# InteractionBoard.net
KiCad netlist of a schematic drawn in EAGLE
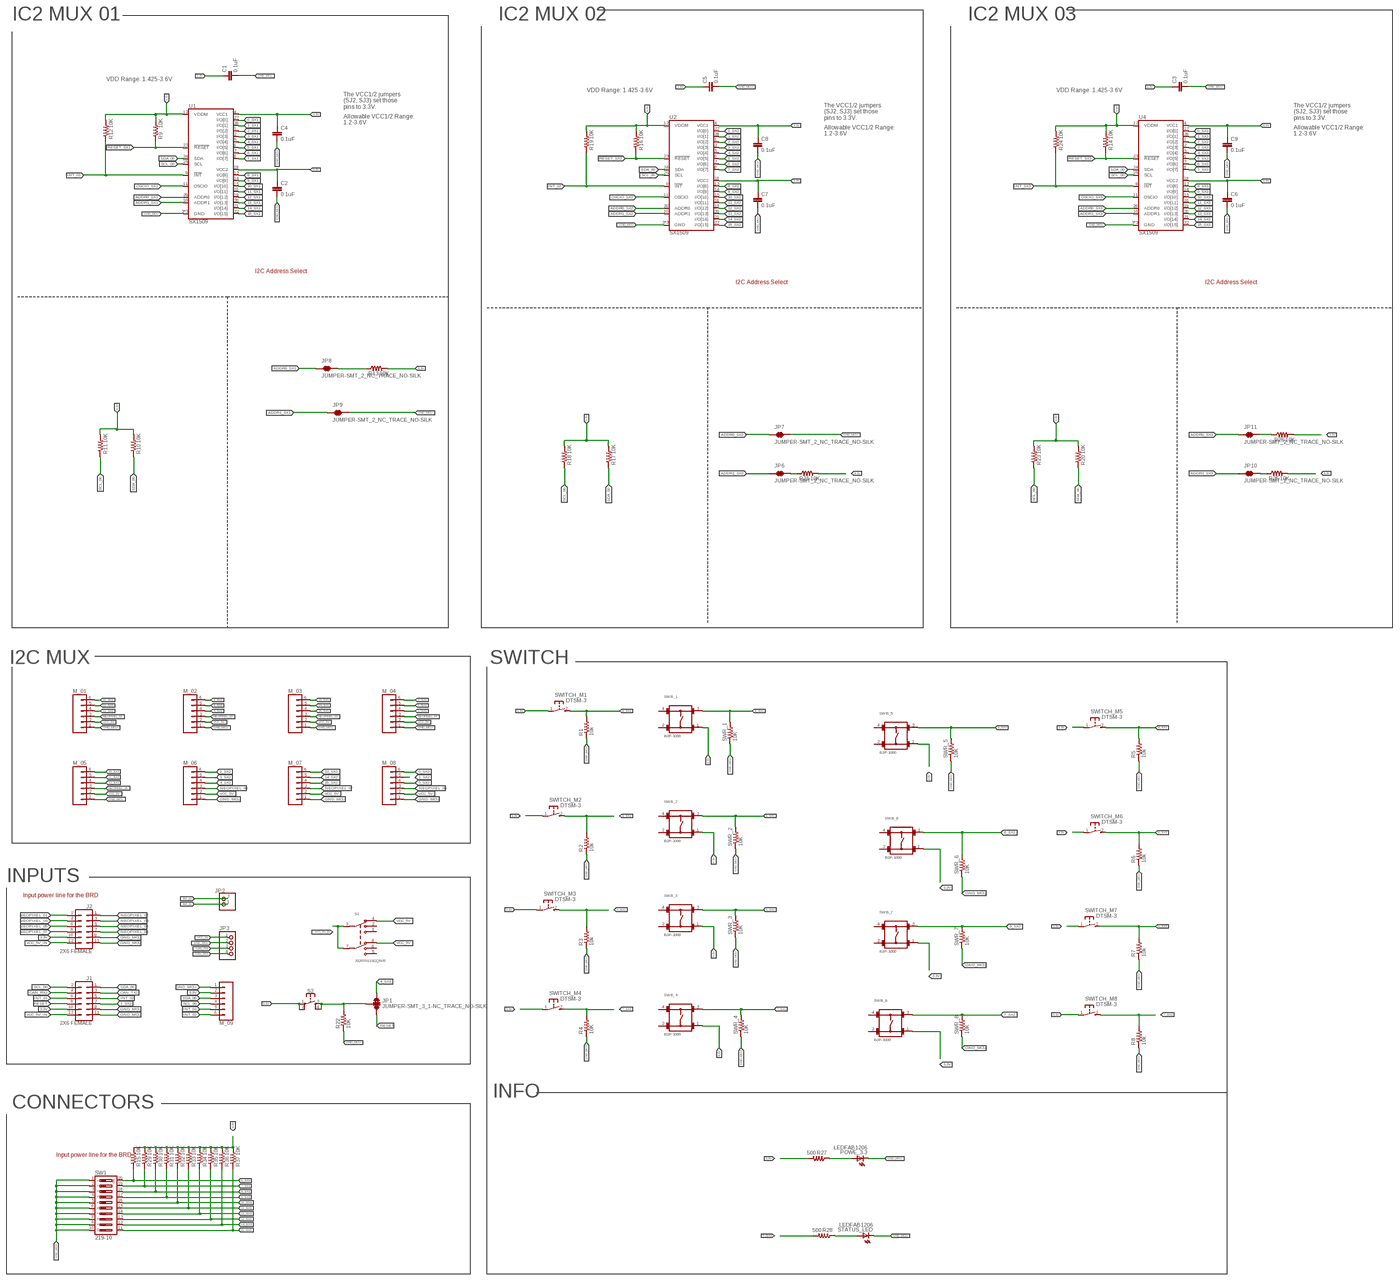
[diagram p0: schematic, sheet 1, overview]
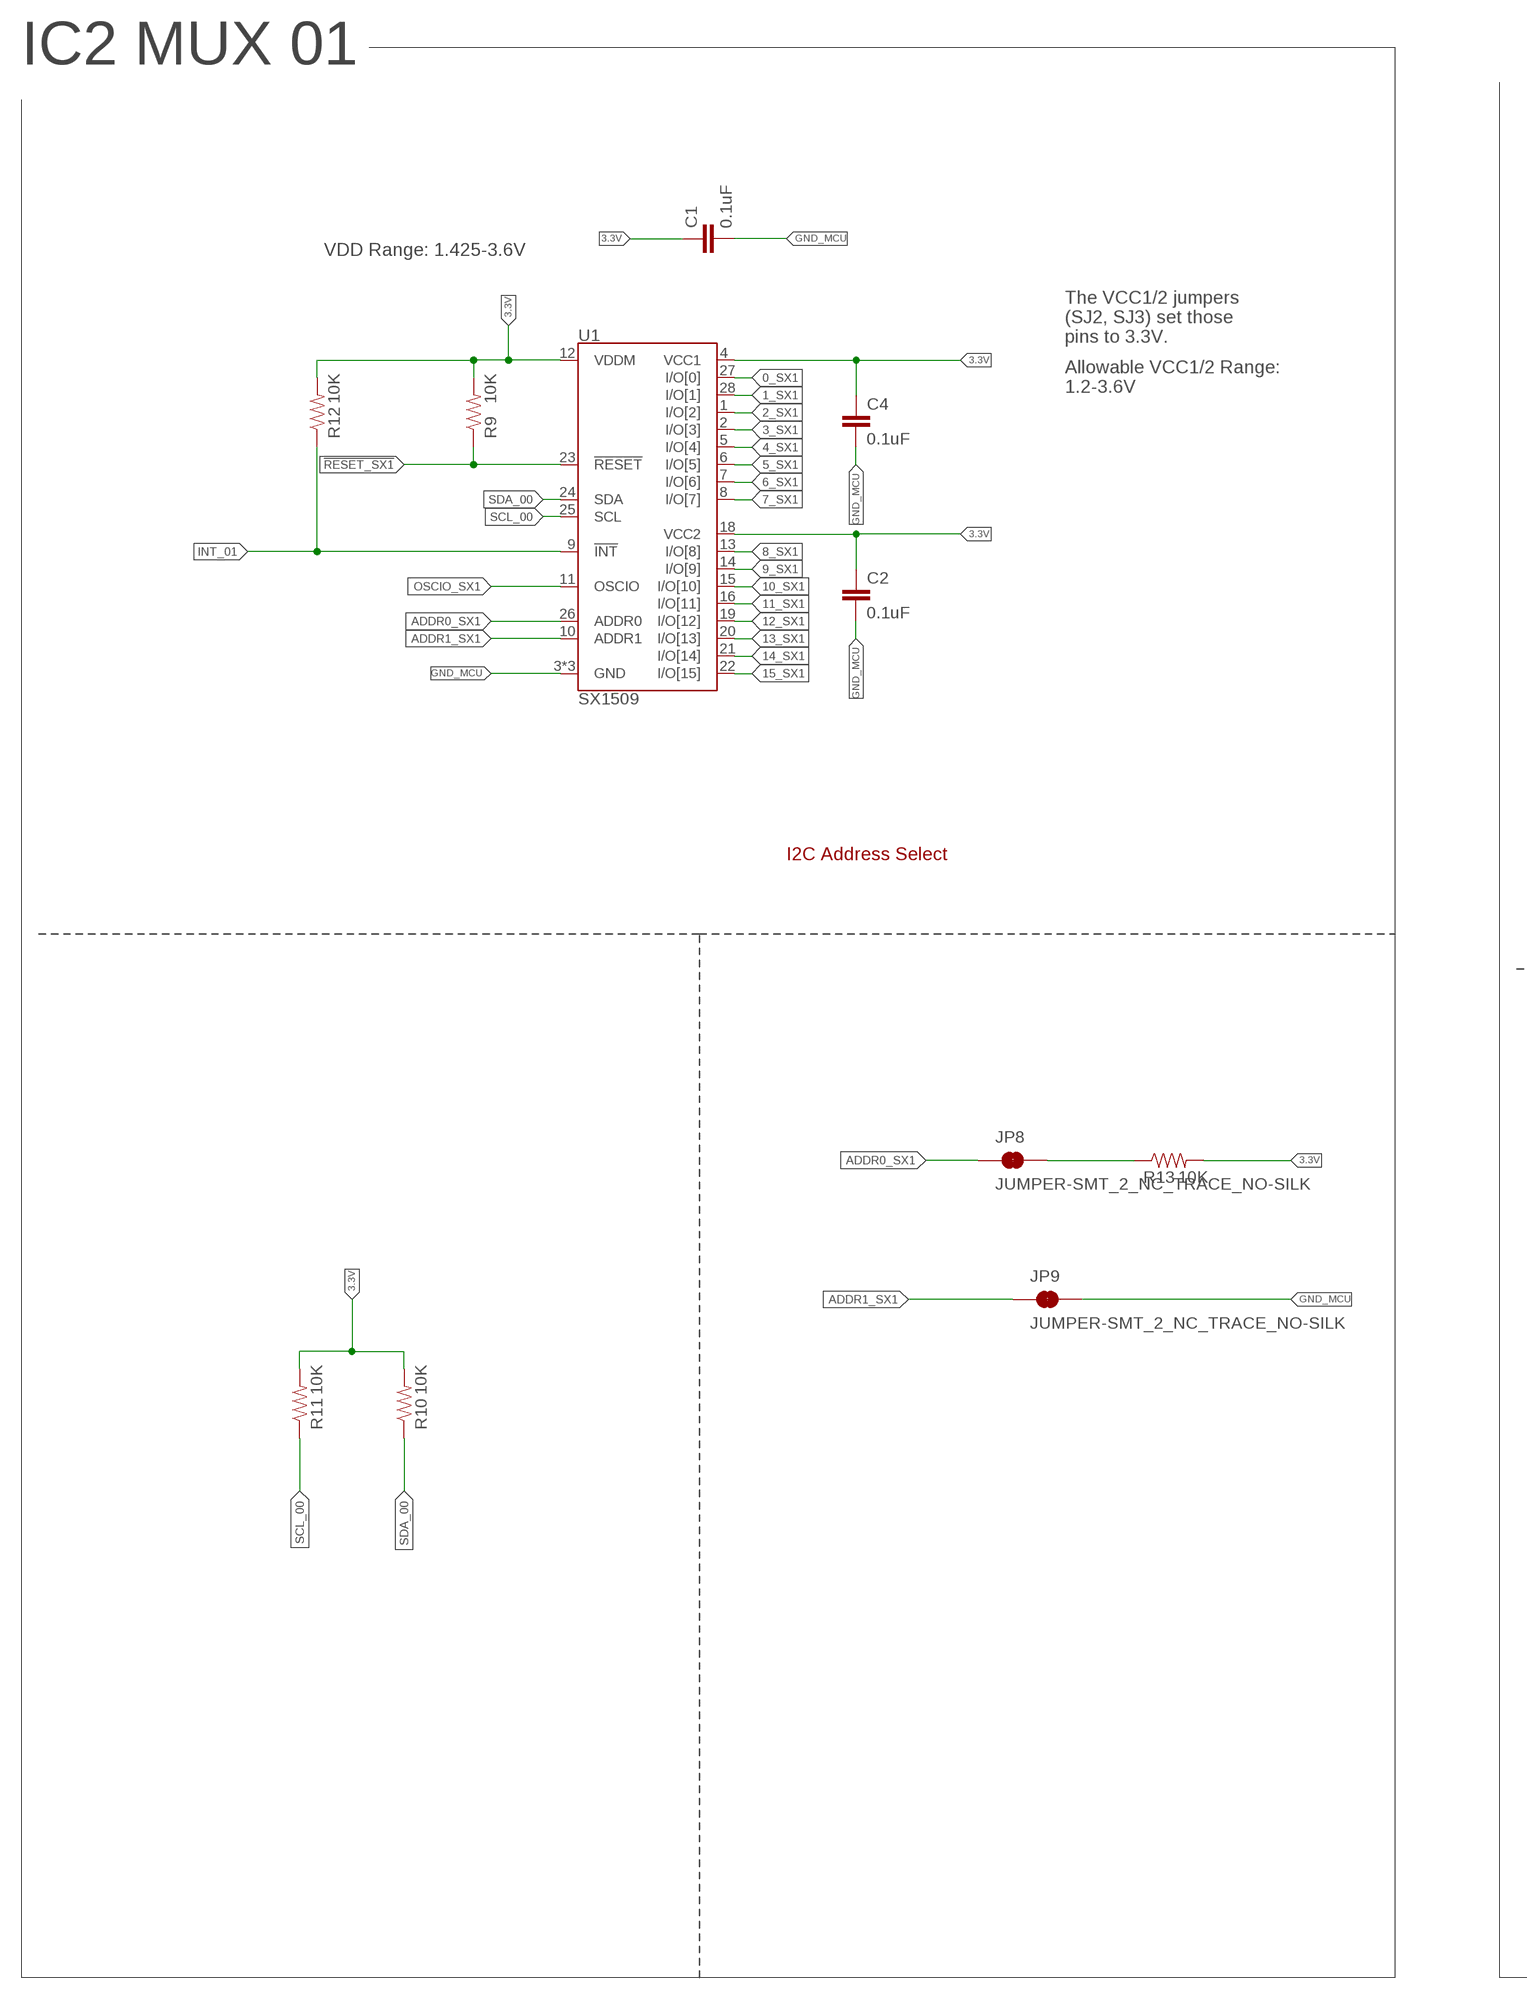
[diagram p1: schematic, sheet 1, part 1 of 4]
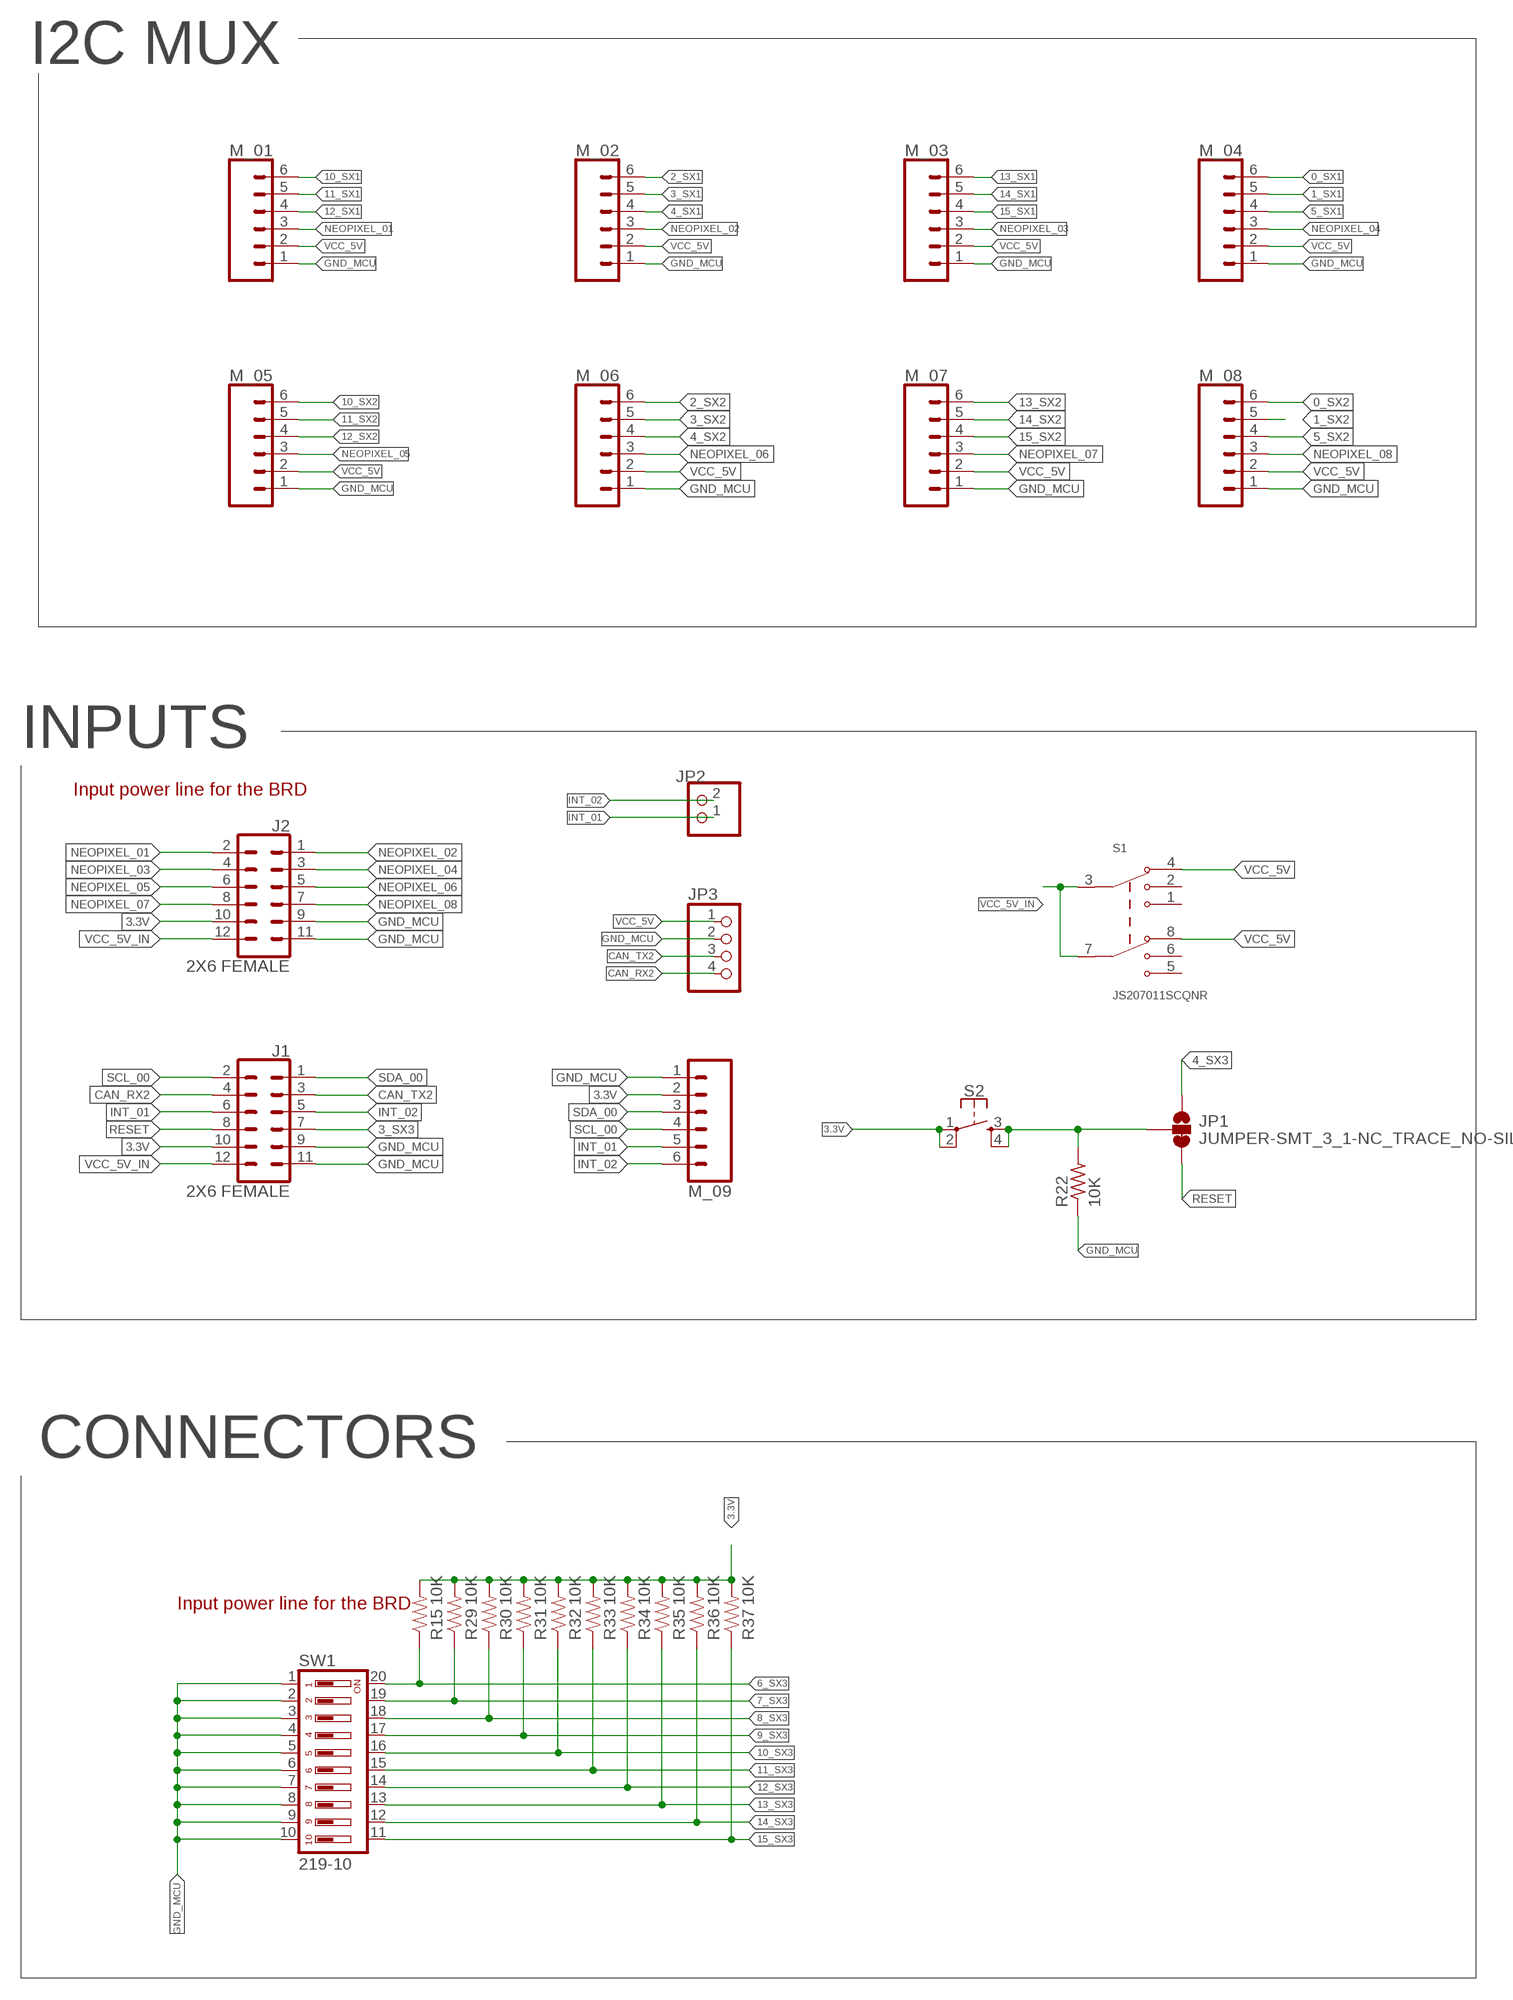
[diagram p2: schematic, sheet 1, part 2 of 4]
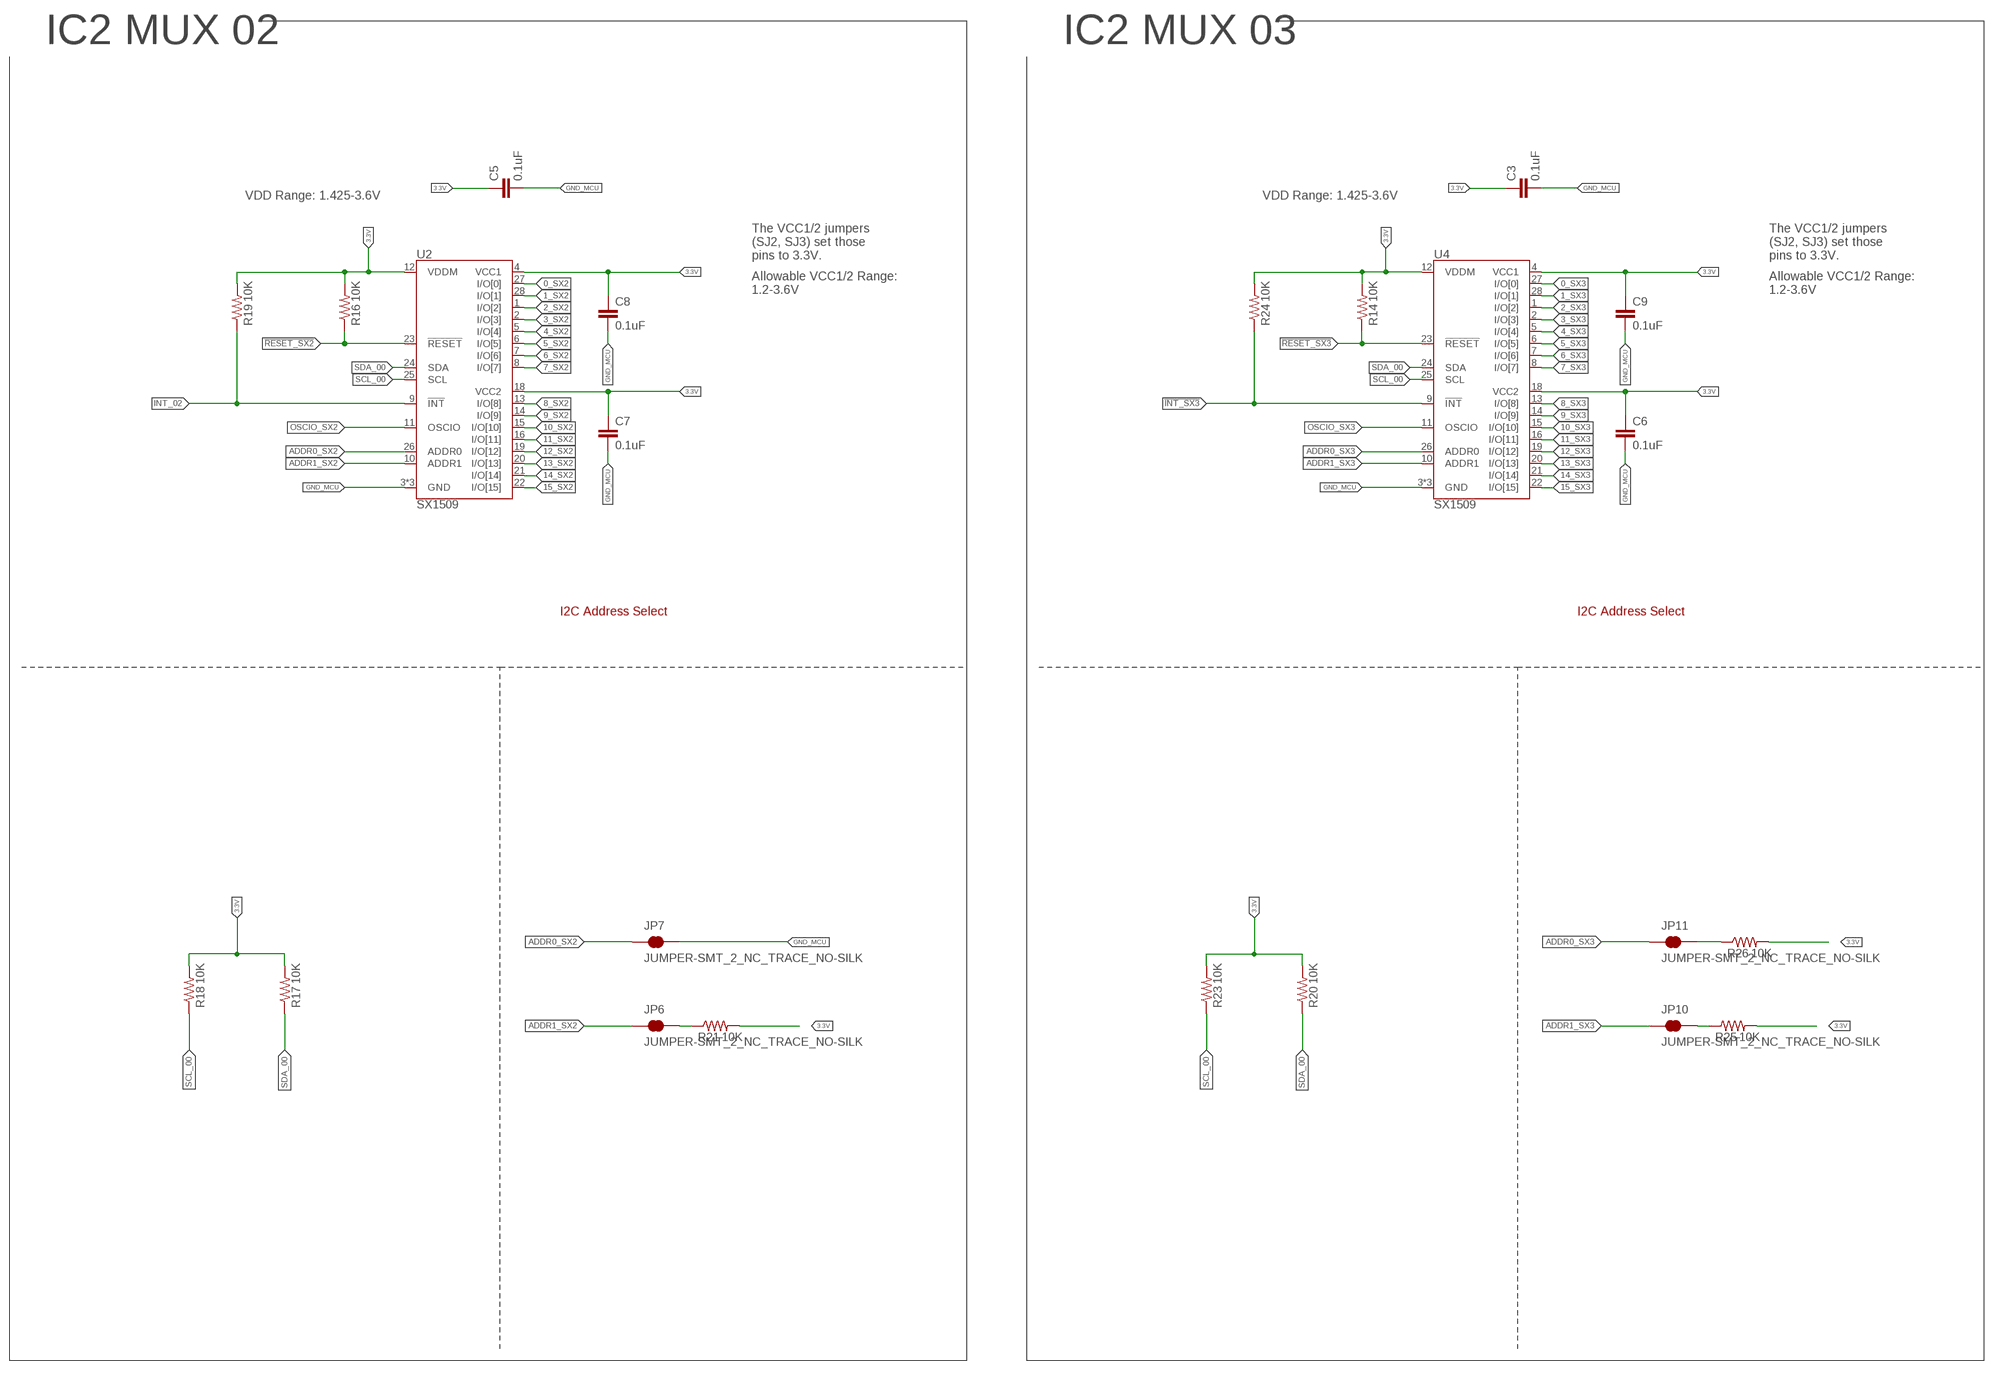
[diagram p3: schematic, sheet 1, part 3 of 4]
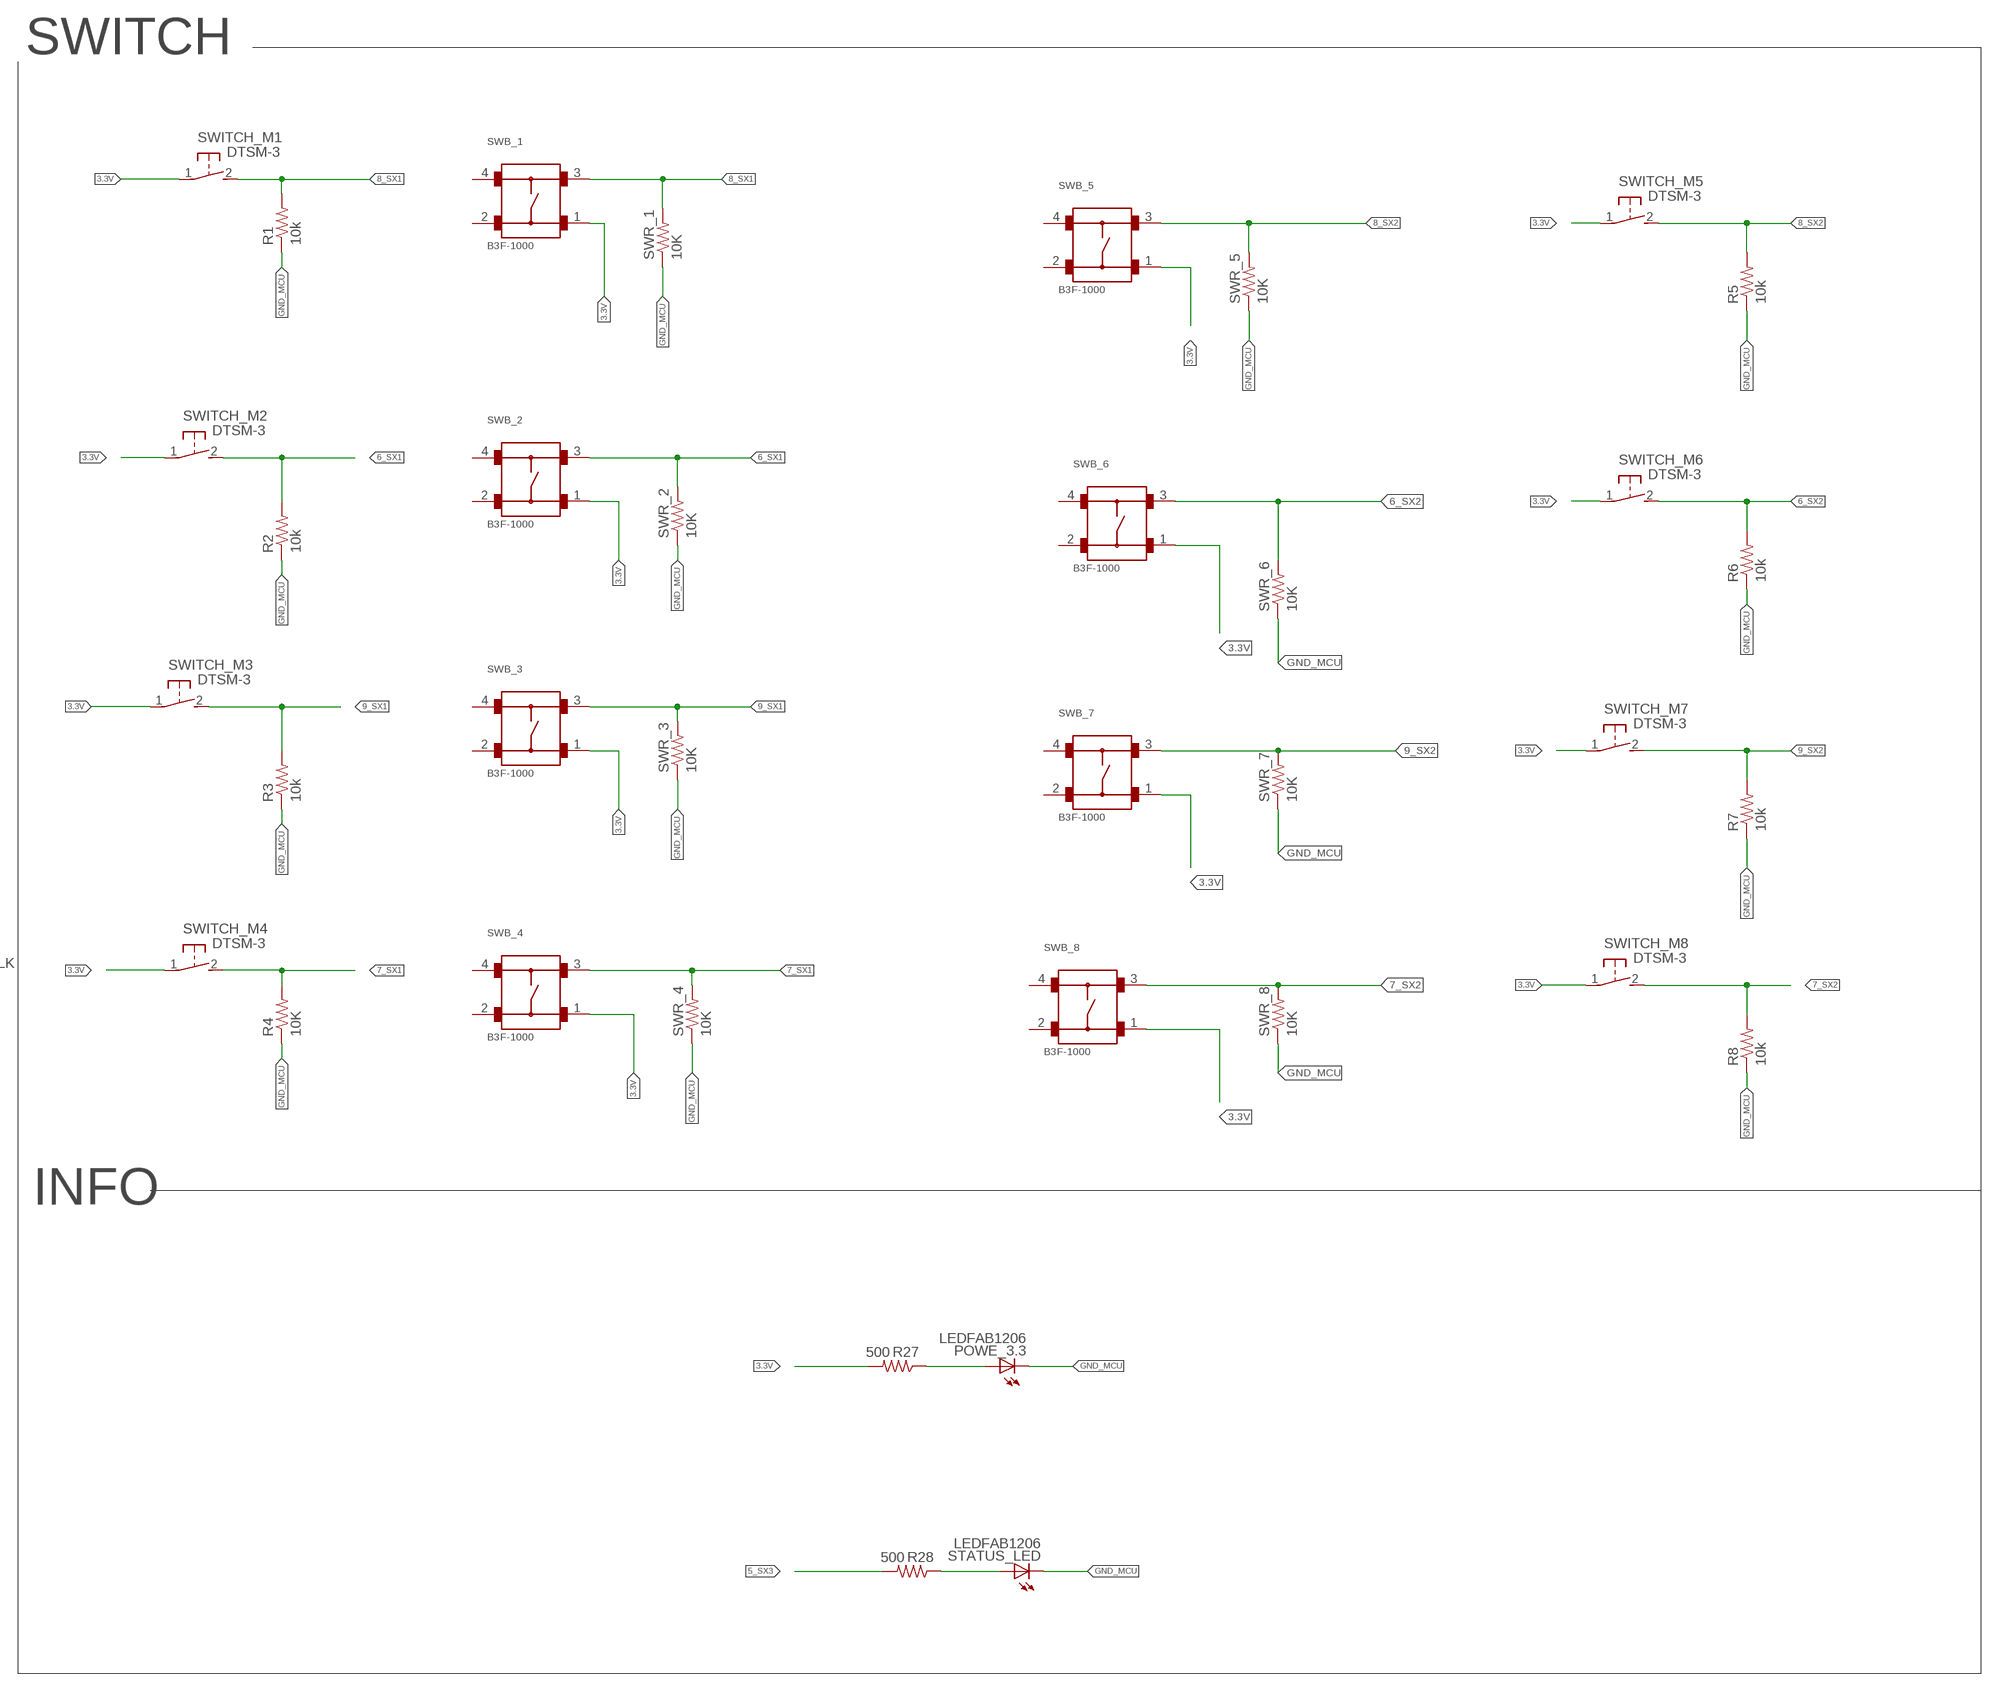
[diagram p4: schematic, sheet 1, part 4 of 4]

(export (version "E")
  (design (tool "Eeschema 10.0.6"))
  (components
    (comp (ref "C1")
      (value "0.1uF")
      (footprint "eagle-import:0603-CAP")
      (libsource (lib "eagle-import") (part "0.1UF-25V(+80/-20%)(0603)"))
    )
    (comp (ref "C2")
      (value "0.1uF")
      (footprint "eagle-import:0603-CAP")
      (libsource (lib "eagle-import") (part "0.1UF-25V(+80/-20%)(0603)"))
    )
    (comp (ref "C3")
      (value "0.1uF")
      (footprint "eagle-import:0603-CAP")
      (libsource (lib "eagle-import") (part "0.1UF-25V(+80/-20%)(0603)"))
    )
    (comp (ref "C4")
      (value "0.1uF")
      (footprint "eagle-import:0603-CAP")
      (libsource (lib "eagle-import") (part "0.1UF-25V(+80/-20%)(0603)"))
    )
    (comp (ref "C5")
      (value "0.1uF")
      (footprint "eagle-import:0603-CAP")
      (libsource (lib "eagle-import") (part "0.1UF-25V(+80/-20%)(0603)"))
    )
    (comp (ref "C6")
      (value "0.1uF")
      (footprint "eagle-import:0603-CAP")
      (libsource (lib "eagle-import") (part "0.1UF-25V(+80/-20%)(0603)"))
    )
    (comp (ref "C7")
      (value "0.1uF")
      (footprint "eagle-import:0603-CAP")
      (libsource (lib "eagle-import") (part "0.1UF-25V(+80/-20%)(0603)"))
    )
    (comp (ref "C8")
      (value "0.1uF")
      (footprint "eagle-import:0603-CAP")
      (libsource (lib "eagle-import") (part "0.1UF-25V(+80/-20%)(0603)"))
    )
    (comp (ref "C9")
      (value "0.1uF")
      (footprint "eagle-import:0603-CAP")
      (libsource (lib "eagle-import") (part "0.1UF-25V(+80/-20%)(0603)"))
    )
    (comp (ref "J1")
      (value "2X6 FEMALE")
      (footprint "eagle-import:2X6")
      (libsource (lib "eagle-import") (part "CONN_06X2PTH_FEMALE"))
    )
    (comp (ref "J2")
      (value "2X6 FEMALE")
      (footprint "eagle-import:2X6")
      (libsource (lib "eagle-import") (part "CONN_06X2PTH_FEMALE"))
    )
    (comp (ref "JP1")
      (value "JUMPER-SMT_3_1-NC_TRACE_NO-SILK")
      (footprint "eagle-import:SMT-JUMPER_3_1-NC_TRACE_NO-SILK")
      (libsource (lib "eagle-import") (part "JUMPER-SMT_3_1-NC_TRACE_NO-SILK"))
    )
    (comp (ref "JP2")
      (value "HEADER-1X2ROUND")
      (footprint "eagle-import:1X02_ROUND")
      (libsource (lib "eagle-import") (part "HEADER-1X2ROUND"))
    )
    (comp (ref "JP3")
      (value "HEADER-1X4ROUND")
      (footprint "eagle-import:1X04_ROUND")
      (libsource (lib "eagle-import") (part "HEADER-1X4ROUND"))
    )
    (comp (ref "JP6")
      (value "JUMPER-SMT_2_NC_TRACE_NO-SILK")
      (footprint "eagle-import:SMT-JUMPER_2_NC_TRACE_NO-SILK")
      (libsource (lib "eagle-import") (part "JUMPER-SMT_2_NC_TRACE_NO-SILK"))
    )
    (comp (ref "JP7")
      (value "JUMPER-SMT_2_NC_TRACE_NO-SILK")
      (footprint "eagle-import:SMT-JUMPER_2_NC_TRACE_NO-SILK")
      (libsource (lib "eagle-import") (part "JUMPER-SMT_2_NC_TRACE_NO-SILK"))
    )
    (comp (ref "JP8")
      (value "JUMPER-SMT_2_NC_TRACE_NO-SILK")
      (footprint "eagle-import:SMT-JUMPER_2_NC_TRACE_NO-SILK")
      (libsource (lib "eagle-import") (part "JUMPER-SMT_2_NC_TRACE_NO-SILK"))
    )
    (comp (ref "JP9")
      (value "JUMPER-SMT_2_NC_TRACE_NO-SILK")
      (footprint "eagle-import:SMT-JUMPER_2_NC_TRACE_NO-SILK")
      (libsource (lib "eagle-import") (part "JUMPER-SMT_2_NC_TRACE_NO-SILK"))
    )
    (comp (ref "JP10")
      (value "JUMPER-SMT_2_NC_TRACE_NO-SILK")
      (footprint "eagle-import:SMT-JUMPER_2_NC_TRACE_NO-SILK")
      (libsource (lib "eagle-import") (part "JUMPER-SMT_2_NC_TRACE_NO-SILK"))
    )
    (comp (ref "JP11")
      (value "JUMPER-SMT_2_NC_TRACE_NO-SILK")
      (footprint "eagle-import:SMT-JUMPER_2_NC_TRACE_NO-SILK")
      (libsource (lib "eagle-import") (part "JUMPER-SMT_2_NC_TRACE_NO-SILK"))
    )
    (comp (ref "M_01")
      (value "CONN_06SMD-1MM")
      (footprint "eagle-import:1X06-1MM")
      (libsource (lib "eagle-import") (part "CONN_06SMD-1MM"))
    )
    (comp (ref "M_02")
      (value "CONN_06SMD-1MM")
      (footprint "eagle-import:1X06-1MM")
      (libsource (lib "eagle-import") (part "CONN_06SMD-1MM"))
    )
    (comp (ref "M_03")
      (value "CONN_06SMD-1MM")
      (footprint "eagle-import:1X06-1MM")
      (libsource (lib "eagle-import") (part "CONN_06SMD-1MM"))
    )
    (comp (ref "M_04")
      (value "CONN_06SMD-1MM")
      (footprint "eagle-import:1X06-1MM")
      (libsource (lib "eagle-import") (part "CONN_06SMD-1MM"))
    )
    (comp (ref "M_05")
      (value "CONN_06SMD-1MM")
      (footprint "eagle-import:1X06-1MM")
      (libsource (lib "eagle-import") (part "CONN_06SMD-1MM"))
    )
    (comp (ref "M_06")
      (value "CONN_06SMD-1MM")
      (footprint "eagle-import:1X06-1MM")
      (libsource (lib "eagle-import") (part "CONN_06SMD-1MM"))
    )
    (comp (ref "M_07")
      (value "CONN_06SMD-1MM")
      (footprint "eagle-import:1X06-1MM")
      (libsource (lib "eagle-import") (part "CONN_06SMD-1MM"))
    )
    (comp (ref "M_08")
      (value "CONN_06SMD-1MM")
      (footprint "eagle-import:1X06-1MM")
      (libsource (lib "eagle-import") (part "CONN_06SMD-1MM"))
    )
    (comp (ref "M_09")
      (value "CONN_06SMD-1MM")
      (footprint "eagle-import:1X06-1MM")
      (libsource (lib "eagle-import") (part "CONN_06SMD-1MM"))
    )
    (comp (ref "POWE_3.3")
      (value "LEDFAB1206")
      (footprint "eagle-import:LED1206FAB")
      (libsource (lib "eagle-import") (part "LEDFAB1206"))
    )
    (comp (ref "R1")
      (value "10k")
      (footprint "eagle-import:M0805")
      (libsource (lib "eagle-import") (part "R-US_M0805"))
    )
    (comp (ref "R2")
      (value "10k")
      (footprint "eagle-import:M0805")
      (libsource (lib "eagle-import") (part "R-US_M0805"))
    )
    (comp (ref "R3")
      (value "10k")
      (footprint "eagle-import:M0805")
      (libsource (lib "eagle-import") (part "R-US_M0805"))
    )
    (comp (ref "R4")
      (value "10K")
      (footprint "eagle-import:M0805")
      (libsource (lib "eagle-import") (part "R-US_M0805"))
    )
    (comp (ref "R5")
      (value "10k")
      (footprint "eagle-import:M0805")
      (libsource (lib "eagle-import") (part "R-US_M0805"))
    )
    (comp (ref "R6")
      (value "10k")
      (footprint "eagle-import:M0805")
      (libsource (lib "eagle-import") (part "R-US_M0805"))
    )
    (comp (ref "R7")
      (value "10k")
      (footprint "eagle-import:M0805")
      (libsource (lib "eagle-import") (part "R-US_M0805"))
    )
    (comp (ref "R8")
      (value "10k")
      (footprint "eagle-import:M0805")
      (libsource (lib "eagle-import") (part "R-US_M0805"))
    )
    (comp (ref "R9")
      (value "10K")
      (footprint "eagle-import:0603-RES")
      (libsource (lib "eagle-import") (part "SparkFun-Resistors_532_10KOHM-1/10W-1%(0603)0603"))
    )
    (comp (ref "R10")
      (value "10K")
      (footprint "eagle-import:0603-RES")
      (libsource (lib "eagle-import") (part "SparkFun-Resistors_532_10KOHM-1/10W-1%(0603)0603"))
    )
    (comp (ref "R11")
      (value "10K")
      (footprint "eagle-import:0603-RES")
      (libsource (lib "eagle-import") (part "SparkFun-Resistors_532_10KOHM-1/10W-1%(0603)0603"))
    )
    (comp (ref "R12")
      (value "10K")
      (footprint "eagle-import:0603-RES")
      (libsource (lib "eagle-import") (part "SparkFun-Resistors_532_10KOHM-1/10W-1%(0603)0603"))
    )
    (comp (ref "R13")
      (value "10K")
      (footprint "eagle-import:0603-RES")
      (libsource (lib "eagle-import") (part "SparkFun-Resistors_532_10KOHM-1/10W-1%(0603)0603"))
    )
    (comp (ref "R14")
      (value "10K")
      (footprint "eagle-import:0603-RES")
      (libsource (lib "eagle-import") (part "SparkFun-Resistors_532_10KOHM-1/10W-1%(0603)0603"))
    )
    (comp (ref "R15")
      (value "10K")
      (footprint "eagle-import:0603-RES")
      (libsource (lib "eagle-import") (part "SparkFun-Resistors_532_10KOHM-1/10W-1%(0603)0603"))
    )
    (comp (ref "R16")
      (value "10K")
      (footprint "eagle-import:0603-RES")
      (libsource (lib "eagle-import") (part "SparkFun-Resistors_532_10KOHM-1/10W-1%(0603)0603"))
    )
    (comp (ref "R17")
      (value "10K")
      (footprint "eagle-import:0603-RES")
      (libsource (lib "eagle-import") (part "SparkFun-Resistors_532_10KOHM-1/10W-1%(0603)0603"))
    )
    (comp (ref "R18")
      (value "10K")
      (footprint "eagle-import:0603-RES")
      (libsource (lib "eagle-import") (part "SparkFun-Resistors_532_10KOHM-1/10W-1%(0603)0603"))
    )
    (comp (ref "R19")
      (value "10K")
      (footprint "eagle-import:0603-RES")
      (libsource (lib "eagle-import") (part "SparkFun-Resistors_532_10KOHM-1/10W-1%(0603)0603"))
    )
    (comp (ref "R20")
      (value "10K")
      (footprint "eagle-import:0603-RES")
      (libsource (lib "eagle-import") (part "SparkFun-Resistors_532_10KOHM-1/10W-1%(0603)0603"))
    )
    (comp (ref "R21")
      (value "10K")
      (footprint "eagle-import:0603-RES")
      (libsource (lib "eagle-import") (part "SparkFun-Resistors_532_10KOHM-1/10W-1%(0603)0603"))
    )
    (comp (ref "R22")
      (value "10K")
      (footprint "eagle-import:M0805")
      (libsource (lib "eagle-import") (part "R-US_M0805"))
    )
    (comp (ref "R23")
      (value "10K")
      (footprint "eagle-import:0603-RES")
      (libsource (lib "eagle-import") (part "SparkFun-Resistors_532_10KOHM-1/10W-1%(0603)0603"))
    )
    (comp (ref "R24")
      (value "10K")
      (footprint "eagle-import:0603-RES")
      (libsource (lib "eagle-import") (part "SparkFun-Resistors_532_10KOHM-1/10W-1%(0603)0603"))
    )
    (comp (ref "R25")
      (value "10K")
      (footprint "eagle-import:0603-RES")
      (libsource (lib "eagle-import") (part "SparkFun-Resistors_532_10KOHM-1/10W-1%(0603)0603"))
    )
    (comp (ref "R26")
      (value "10K")
      (footprint "eagle-import:0603-RES")
      (libsource (lib "eagle-import") (part "SparkFun-Resistors_532_10KOHM-1/10W-1%(0603)0603"))
    )
    (comp (ref "R27")
      (value "500")
      (footprint "eagle-import:0603-RES")
      (libsource (lib "eagle-import") (part "10KOHM-1/10W-1%(0603)0603"))
    )
    (comp (ref "R28")
      (value "500")
      (footprint "eagle-import:0603-RES")
      (libsource (lib "eagle-import") (part "10KOHM-1/10W-1%(0603)0603"))
    )
    (comp (ref "R29")
      (value "10K")
      (footprint "eagle-import:0603-RES")
      (libsource (lib "eagle-import") (part "SparkFun-Resistors_532_10KOHM-1/10W-1%(0603)0603"))
    )
    (comp (ref "R30")
      (value "10K")
      (footprint "eagle-import:0603-RES")
      (libsource (lib "eagle-import") (part "SparkFun-Resistors_532_10KOHM-1/10W-1%(0603)0603"))
    )
    (comp (ref "R31")
      (value "10K")
      (footprint "eagle-import:0603-RES")
      (libsource (lib "eagle-import") (part "SparkFun-Resistors_532_10KOHM-1/10W-1%(0603)0603"))
    )
    (comp (ref "R32")
      (value "10K")
      (footprint "eagle-import:0603-RES")
      (libsource (lib "eagle-import") (part "SparkFun-Resistors_532_10KOHM-1/10W-1%(0603)0603"))
    )
    (comp (ref "R33")
      (value "10K")
      (footprint "eagle-import:0603-RES")
      (libsource (lib "eagle-import") (part "SparkFun-Resistors_532_10KOHM-1/10W-1%(0603)0603"))
    )
    (comp (ref "R34")
      (value "10K")
      (footprint "eagle-import:0603-RES")
      (libsource (lib "eagle-import") (part "SparkFun-Resistors_532_10KOHM-1/10W-1%(0603)0603"))
    )
    (comp (ref "R35")
      (value "10K")
      (footprint "eagle-import:0603-RES")
      (libsource (lib "eagle-import") (part "SparkFun-Resistors_532_10KOHM-1/10W-1%(0603)0603"))
    )
    (comp (ref "R36")
      (value "10K")
      (footprint "eagle-import:0603-RES")
      (libsource (lib "eagle-import") (part "SparkFun-Resistors_532_10KOHM-1/10W-1%(0603)0603"))
    )
    (comp (ref "R37")
      (value "10K")
      (footprint "eagle-import:0603-RES")
      (libsource (lib "eagle-import") (part "SparkFun-Resistors_532_10KOHM-1/10W-1%(0603)0603"))
    )
    (comp (ref "S1")
      (value "JS207011SCQNR")
      (footprint "eagle-import:SW_JS207011SCQNR")
      (fields (field (name "MF") "C&K"))
      (libsource (lib "eagle-import") (part "JS207011SCQNR"))
    )
    (comp (ref "S2")
      (value "MOMENTARY-SWITCH-SPST-2-SMD-5.2MM")
      (footprint "eagle-import:TACTILE_SWITCH_SMD_5.2MM")
      (libsource (lib "eagle-import") (part "MOMENTARY-SWITCH-SPST-2-SMD-5.2MM"))
    )
    (comp (ref "STATUS_LED")
      (value "LEDFAB1206")
      (footprint "eagle-import:LED1206FAB")
      (libsource (lib "eagle-import") (part "LEDFAB1206"))
    )
    (comp (ref "SW1")
      (value "219-10")
      (footprint "eagle-import:CTS-219-10")
      (fields (field (name "MF") "SLI (CML/IDI)") (field (name "MPN") "219-10PK"))
      (libsource (lib "eagle-import") (part "219-10"))
    )
    (comp (ref "SWB_1")
      (value "B3F-1000")
      (footprint "eagle-import:B3F-1000")
      (fields
        (field (name "DIGI_KEY_PART_NUMBER") "SW400-ND")
        (field (name "MANUFACTURER") "Omron Electronics Inc-EMC Div")
        (field (name "CREATED_BY") "PCBLayout.com")
      )
      (libsource (lib "eagle-import") (part "B3F-1000"))
    )
    (comp (ref "SWB_2")
      (value "B3F-1000")
      (footprint "eagle-import:B3F-1000")
      (fields
        (field (name "DIGI_KEY_PART_NUMBER") "SW400-ND")
        (field (name "MANUFACTURER") "Omron Electronics Inc-EMC Div")
        (field (name "CREATED_BY") "PCBLayout.com")
      )
      (libsource (lib "eagle-import") (part "B3F-1000"))
    )
    (comp (ref "SWB_3")
      (value "B3F-1000")
      (footprint "eagle-import:B3F-1000")
      (fields
        (field (name "DIGI_KEY_PART_NUMBER") "SW400-ND")
        (field (name "MANUFACTURER") "Omron Electronics Inc-EMC Div")
        (field (name "CREATED_BY") "PCBLayout.com")
      )
      (libsource (lib "eagle-import") (part "B3F-1000"))
    )
    (comp (ref "SWB_4")
      (value "B3F-1000")
      (footprint "eagle-import:B3F-1000")
      (fields
        (field (name "DIGI_KEY_PART_NUMBER") "SW400-ND")
        (field (name "MANUFACTURER") "Omron Electronics Inc-EMC Div")
        (field (name "CREATED_BY") "PCBLayout.com")
      )
      (libsource (lib "eagle-import") (part "B3F-1000"))
    )
    (comp (ref "SWB_5")
      (value "B3F-1000")
      (footprint "eagle-import:B3F-1000")
      (fields
        (field (name "DIGI_KEY_PART_NUMBER") "SW400-ND")
        (field (name "MANUFACTURER") "Omron Electronics Inc-EMC Div")
        (field (name "CREATED_BY") "PCBLayout.com")
      )
      (libsource (lib "eagle-import") (part "B3F-1000"))
    )
    (comp (ref "SWB_6")
      (value "B3F-1000")
      (footprint "eagle-import:B3F-1000")
      (fields
        (field (name "DIGI_KEY_PART_NUMBER") "SW400-ND")
        (field (name "MANUFACTURER") "Omron Electronics Inc-EMC Div")
        (field (name "CREATED_BY") "PCBLayout.com")
      )
      (libsource (lib "eagle-import") (part "B3F-1000"))
    )
    (comp (ref "SWB_7")
      (value "B3F-1000")
      (footprint "eagle-import:B3F-1000")
      (fields
        (field (name "DIGI_KEY_PART_NUMBER") "SW400-ND")
        (field (name "MANUFACTURER") "Omron Electronics Inc-EMC Div")
        (field (name "CREATED_BY") "PCBLayout.com")
      )
      (libsource (lib "eagle-import") (part "B3F-1000"))
    )
    (comp (ref "SWB_8")
      (value "B3F-1000")
      (footprint "eagle-import:B3F-1000")
      (fields
        (field (name "DIGI_KEY_PART_NUMBER") "SW400-ND")
        (field (name "MANUFACTURER") "Omron Electronics Inc-EMC Div")
        (field (name "CREATED_BY") "PCBLayout.com")
      )
      (libsource (lib "eagle-import") (part "B3F-1000"))
    )
    (comp (ref "SWITCH_M1")
      (value "DTSM-3")
      (footprint "eagle-import:DTSM-3")
      (libsource (lib "eagle-import") (part "DTSM-3"))
    )
    (comp (ref "SWITCH_M2")
      (value "DTSM-3")
      (footprint "eagle-import:DTSM-3")
      (libsource (lib "eagle-import") (part "DTSM-3"))
    )
    (comp (ref "SWITCH_M3")
      (value "DTSM-3")
      (footprint "eagle-import:DTSM-3")
      (libsource (lib "eagle-import") (part "DTSM-3"))
    )
    (comp (ref "SWITCH_M4")
      (value "DTSM-3")
      (footprint "eagle-import:DTSM-3")
      (libsource (lib "eagle-import") (part "DTSM-3"))
    )
    (comp (ref "SWITCH_M5")
      (value "DTSM-3")
      (footprint "eagle-import:DTSM-3")
      (libsource (lib "eagle-import") (part "DTSM-3"))
    )
    (comp (ref "SWITCH_M6")
      (value "DTSM-3")
      (footprint "eagle-import:DTSM-3")
      (libsource (lib "eagle-import") (part "DTSM-3"))
    )
    (comp (ref "SWITCH_M7")
      (value "DTSM-3")
      (footprint "eagle-import:DTSM-3")
      (libsource (lib "eagle-import") (part "DTSM-3"))
    )
    (comp (ref "SWITCH_M8")
      (value "DTSM-3")
      (footprint "eagle-import:DTSM-3")
      (libsource (lib "eagle-import") (part "DTSM-3"))
    )
    (comp (ref "SWR_1")
      (value "10K")
      (footprint "eagle-import:M0805")
      (libsource (lib "eagle-import") (part "R-US_M0805"))
    )
    (comp (ref "SWR_2")
      (value "10K")
      (footprint "eagle-import:M0805")
      (libsource (lib "eagle-import") (part "R-US_M0805"))
    )
    (comp (ref "SWR_3")
      (value "10K")
      (footprint "eagle-import:M0805")
      (libsource (lib "eagle-import") (part "R-US_M0805"))
    )
    (comp (ref "SWR_4")
      (value "10K")
      (footprint "eagle-import:M0805")
      (libsource (lib "eagle-import") (part "R-US_M0805"))
    )
    (comp (ref "SWR_5")
      (value "10K")
      (footprint "eagle-import:M0805")
      (libsource (lib "eagle-import") (part "R-US_M0805"))
    )
    (comp (ref "SWR_6")
      (value "10K")
      (footprint "eagle-import:M0805")
      (libsource (lib "eagle-import") (part "R-US_M0805"))
    )
    (comp (ref "SWR_7")
      (value "10K")
      (footprint "eagle-import:M0805")
      (libsource (lib "eagle-import") (part "R-US_M0805"))
    )
    (comp (ref "SWR_8")
      (value "10K")
      (footprint "eagle-import:M0805")
      (libsource (lib "eagle-import") (part "R-US_M0805"))
    )
    (comp (ref "U1")
      (value "SX1509")
      (footprint "eagle-import:QFN-28")
      (libsource (lib "eagle-import") (part "SX1509"))
    )
    (comp (ref "U2")
      (value "SX1509")
      (footprint "eagle-import:QFN-28")
      (libsource (lib "eagle-import") (part "SX1509"))
    )
    (comp (ref "U4")
      (value "SX1509")
      (footprint "eagle-import:QFN-28")
      (libsource (lib "eagle-import") (part "SX1509"))
    )
  )
  (nets
    (net (code "1") (name "/~{INT_SX3}") (class "Default")
      (node (ref "R24") (pin "1") (pinfunction "1_1") (pintype "passive"))
      (node (ref "U4") (pin "9") (pinfunction "~{INT}_9") (pintype "bidirectional"))
    )
    (net (code "2") (name "/~{RESET_SX1}") (class "Default")
      (node (ref "R9") (pin "1") (pinfunction "1_1") (pintype "passive"))
      (node (ref "U1") (pin "23") (pinfunction "~{RESET}_23") (pintype "bidirectional"))
    )
    (net (code "3") (name "/~{RESET_SX2}") (class "Default")
      (node (ref "R16") (pin "1") (pinfunction "1_1") (pintype "passive"))
      (node (ref "U2") (pin "23") (pinfunction "~{RESET}_23") (pintype "bidirectional"))
    )
    (net (code "4") (name "/~{RESET_SX3}") (class "Default")
      (node (ref "R14") (pin "1") (pinfunction "1_1") (pintype "passive"))
      (node (ref "U4") (pin "23") (pinfunction "~{RESET}_23") (pintype "bidirectional"))
    )
    (net (code "5") (name "0_SX1") (class "Default")
      (node (ref "M_04") (pin "6") (pinfunction "6_6") (pintype "passive"))
      (node (ref "U1") (pin "27") (pinfunction "I/O[0]_27") (pintype "bidirectional"))
    )
    (net (code "6") (name "0_SX2") (class "Default")
      (node (ref "M_08") (pin "6") (pinfunction "6_6") (pintype "passive"))
      (node (ref "U2") (pin "27") (pinfunction "I/O[0]_27") (pintype "bidirectional"))
    )
    (net (code "7") (name "0_SX3") (class "Default")
      (node (ref "U4") (pin "27") (pinfunction "I/O[0]_27") (pintype "bidirectional"))
    )
    (net (code "8") (name "1_SX1") (class "Default")
      (node (ref "M_04") (pin "5") (pinfunction "5_5") (pintype "passive"))
      (node (ref "U1") (pin "28") (pinfunction "I/O[1]_28") (pintype "bidirectional"))
    )
    (net (code "9") (name "1_SX2") (class "Default")
      (node (ref "M_08") (pin "5") (pinfunction "5_5") (pintype "passive"))
      (node (ref "U2") (pin "28") (pinfunction "I/O[1]_28") (pintype "bidirectional"))
    )
    (net (code "10") (name "1_SX3") (class "Default")
      (node (ref "U4") (pin "28") (pinfunction "I/O[1]_28") (pintype "bidirectional"))
    )
    (net (code "11") (name "2_SX1") (class "Default")
      (node (ref "M_02") (pin "6") (pinfunction "6_6") (pintype "passive"))
      (node (ref "U1") (pin "1") (pinfunction "I/O[2]_1") (pintype "bidirectional"))
    )
    (net (code "12") (name "2_SX2") (class "Default")
      (node (ref "M_06") (pin "6") (pinfunction "6_6") (pintype "passive"))
      (node (ref "U2") (pin "1") (pinfunction "I/O[2]_1") (pintype "bidirectional"))
    )
    (net (code "13") (name "2_SX3") (class "Default")
      (node (ref "U4") (pin "1") (pinfunction "I/O[2]_1") (pintype "bidirectional"))
    )
    (net (code "14") (name "3.3V") (class "Default")
      (node (ref "C1") (pin "1") (pinfunction "1_1") (pintype "passive"))
      (node (ref "C2") (pin "1") (pinfunction "1_1") (pintype "passive"))
      (node (ref "C3") (pin "1") (pinfunction "1_1") (pintype "passive"))
      (node (ref "C4") (pin "1") (pinfunction "1_1") (pintype "passive"))
      (node (ref "C5") (pin "1") (pinfunction "1_1") (pintype "passive"))
      (node (ref "C6") (pin "1") (pinfunction "1_1") (pintype "passive"))
      (node (ref "C7") (pin "1") (pinfunction "1_1") (pintype "passive"))
      (node (ref "C8") (pin "1") (pinfunction "1_1") (pintype "passive"))
      (node (ref "C9") (pin "1") (pinfunction "1_1") (pintype "passive"))
      (node (ref "J1") (pin "10") (pinfunction "10_10") (pintype "passive"))
      (node (ref "J2") (pin "10") (pinfunction "10_10") (pintype "passive"))
      (node (ref "M_09") (pin "2") (pinfunction "2_2") (pintype "passive"))
      (node (ref "R10") (pin "2") (pinfunction "2_2") (pintype "passive"))
      (node (ref "R11") (pin "2") (pinfunction "2_2") (pintype "passive"))
      (node (ref "R12") (pin "2") (pinfunction "2_2") (pintype "passive"))
      (node (ref "R13") (pin "2") (pinfunction "2_2") (pintype "passive"))
      (node (ref "R14") (pin "2") (pinfunction "2_2") (pintype "passive"))
      (node (ref "R15") (pin "2") (pinfunction "2_2") (pintype "passive"))
      (node (ref "R16") (pin "2") (pinfunction "2_2") (pintype "passive"))
      (node (ref "R17") (pin "2") (pinfunction "2_2") (pintype "passive"))
      (node (ref "R18") (pin "2") (pinfunction "2_2") (pintype "passive"))
      (node (ref "R19") (pin "2") (pinfunction "2_2") (pintype "passive"))
      (node (ref "R20") (pin "2") (pinfunction "2_2") (pintype "passive"))
      (node (ref "R21") (pin "2") (pinfunction "2_2") (pintype "passive"))
      (node (ref "R23") (pin "2") (pinfunction "2_2") (pintype "passive"))
      (node (ref "R24") (pin "2") (pinfunction "2_2") (pintype "passive"))
      (node (ref "R25") (pin "2") (pinfunction "2_2") (pintype "passive"))
      (node (ref "R26") (pin "2") (pinfunction "2_2") (pintype "passive"))
      (node (ref "R27") (pin "2") (pinfunction "2_2") (pintype "passive"))
      (node (ref "R29") (pin "2") (pinfunction "2_2") (pintype "passive"))
      (node (ref "R30") (pin "2") (pinfunction "2_2") (pintype "passive"))
      (node (ref "R31") (pin "2") (pinfunction "2_2") (pintype "passive"))
      (node (ref "R32") (pin "2") (pinfunction "2_2") (pintype "passive"))
      (node (ref "R33") (pin "2") (pinfunction "2_2") (pintype "passive"))
      (node (ref "R34") (pin "2") (pinfunction "2_2") (pintype "passive"))
      (node (ref "R35") (pin "2") (pinfunction "2_2") (pintype "passive"))
      (node (ref "R36") (pin "2") (pinfunction "2_2") (pintype "passive"))
      (node (ref "R37") (pin "2") (pinfunction "2_2") (pintype "passive"))
      (node (ref "R9") (pin "2") (pinfunction "2_2") (pintype "passive"))
      (node (ref "S2") (pin "1") (pinfunction "1_1") (pintype "passive"))
      (node (ref "S2") (pin "2") (pinfunction "2_2") (pintype "passive"))
      (node (ref "SWB_1") (pin "1") (pinfunction "1_1") (pintype "passive"))
      (node (ref "SWB_2") (pin "1") (pinfunction "1_1") (pintype "passive"))
      (node (ref "SWB_3") (pin "1") (pinfunction "1_1") (pintype "passive"))
      (node (ref "SWB_4") (pin "1") (pinfunction "1_1") (pintype "passive"))
      (node (ref "SWB_5") (pin "1") (pinfunction "1_1") (pintype "passive"))
      (node (ref "SWB_6") (pin "1") (pinfunction "1_1") (pintype "passive"))
      (node (ref "SWB_7") (pin "1") (pinfunction "1_1") (pintype "passive"))
      (node (ref "SWB_8") (pin "1") (pinfunction "1_1") (pintype "passive"))
      (node (ref "SWITCH_M1") (pin "1") (pinfunction "1_1") (pintype "passive"))
      (node (ref "SWITCH_M2") (pin "1") (pinfunction "1_1") (pintype "passive"))
      (node (ref "SWITCH_M3") (pin "1") (pinfunction "1_1") (pintype "passive"))
      (node (ref "SWITCH_M4") (pin "1") (pinfunction "1_1") (pintype "passive"))
      (node (ref "SWITCH_M5") (pin "1") (pinfunction "1_1") (pintype "passive"))
      (node (ref "SWITCH_M6") (pin "1") (pinfunction "1_1") (pintype "passive"))
      (node (ref "SWITCH_M7") (pin "1") (pinfunction "1_1") (pintype "passive"))
      (node (ref "SWITCH_M8") (pin "1") (pinfunction "1_1") (pintype "passive"))
      (node (ref "U1") (pin "12") (pinfunction "VDDM_12") (pintype "bidirectional"))
      (node (ref "U1") (pin "18") (pinfunction "VCC2_18") (pintype "bidirectional"))
      (node (ref "U1") (pin "4") (pinfunction "VCC1_4") (pintype "bidirectional"))
      (node (ref "U2") (pin "12") (pinfunction "VDDM_12") (pintype "bidirectional"))
      (node (ref "U2") (pin "18") (pinfunction "VCC2_18") (pintype "bidirectional"))
      (node (ref "U2") (pin "4") (pinfunction "VCC1_4") (pintype "bidirectional"))
      (node (ref "U4") (pin "12") (pinfunction "VDDM_12") (pintype "bidirectional"))
      (node (ref "U4") (pin "18") (pinfunction "VCC2_18") (pintype "bidirectional"))
      (node (ref "U4") (pin "4") (pinfunction "VCC1_4") (pintype "bidirectional"))
    )
    (net (code "15") (name "3_SX1") (class "Default")
      (node (ref "M_02") (pin "5") (pinfunction "5_5") (pintype "passive"))
      (node (ref "U1") (pin "2") (pinfunction "I/O[3]_2") (pintype "bidirectional"))
    )
    (net (code "16") (name "3_SX2") (class "Default")
      (node (ref "M_06") (pin "5") (pinfunction "5_5") (pintype "passive"))
      (node (ref "U2") (pin "2") (pinfunction "I/O[3]_2") (pintype "bidirectional"))
    )
    (net (code "17") (name "3_SX3") (class "Default")
      (node (ref "J1") (pin "7") (pinfunction "7_7") (pintype "passive"))
      (node (ref "U4") (pin "2") (pinfunction "I/O[3]_2") (pintype "bidirectional"))
    )
    (net (code "18") (name "4_SX1") (class "Default")
      (node (ref "M_02") (pin "4") (pinfunction "4_4") (pintype "passive"))
      (node (ref "U1") (pin "5") (pinfunction "I/O[4]_5") (pintype "bidirectional"))
    )
    (net (code "19") (name "4_SX2") (class "Default")
      (node (ref "M_06") (pin "4") (pinfunction "4_4") (pintype "passive"))
      (node (ref "U2") (pin "5") (pinfunction "I/O[4]_5") (pintype "bidirectional"))
    )
    (net (code "20") (name "4_SX3") (class "Default")
      (node (ref "JP1") (pin "1") (pinfunction "1_1") (pintype "passive"))
      (node (ref "U4") (pin "5") (pinfunction "I/O[4]_5") (pintype "bidirectional"))
    )
    (net (code "21") (name "5_SX1") (class "Default")
      (node (ref "M_04") (pin "4") (pinfunction "4_4") (pintype "passive"))
      (node (ref "U1") (pin "6") (pinfunction "I/O[5]_6") (pintype "bidirectional"))
    )
    (net (code "22") (name "5_SX2") (class "Default")
      (node (ref "M_08") (pin "4") (pinfunction "4_4") (pintype "passive"))
      (node (ref "U2") (pin "6") (pinfunction "I/O[5]_6") (pintype "bidirectional"))
    )
    (net (code "23") (name "5_SX3") (class "Default")
      (node (ref "R28") (pin "2") (pinfunction "2_2") (pintype "passive"))
      (node (ref "U4") (pin "6") (pinfunction "I/O[5]_6") (pintype "bidirectional"))
    )
    (net (code "24") (name "6_SX1") (class "Default")
      (node (ref "R2") (pin "2") (pinfunction "2_2") (pintype "passive"))
      (node (ref "SWB_2") (pin "3") (pinfunction "3_3") (pintype "passive"))
      (node (ref "SWITCH_M2") (pin "2") (pinfunction "2_2") (pintype "passive"))
      (node (ref "SWR_2") (pin "2") (pinfunction "2_2") (pintype "passive"))
      (node (ref "U1") (pin "7") (pinfunction "I/O[6]_7") (pintype "bidirectional"))
    )
    (net (code "25") (name "6_SX2") (class "Default")
      (node (ref "R6") (pin "2") (pinfunction "2_2") (pintype "passive"))
      (node (ref "SWB_6") (pin "3") (pinfunction "3_3") (pintype "passive"))
      (node (ref "SWITCH_M6") (pin "2") (pinfunction "2_2") (pintype "passive"))
      (node (ref "SWR_6") (pin "2") (pinfunction "2_2") (pintype "passive"))
      (node (ref "U2") (pin "7") (pinfunction "I/O[6]_7") (pintype "bidirectional"))
    )
    (net (code "26") (name "6_SX3") (class "Default")
      (node (ref "R15") (pin "1") (pinfunction "1_1") (pintype "passive"))
      (node (ref "SW1") (pin "20") (pinfunction "20_20") (pintype "passive"))
      (node (ref "U4") (pin "7") (pinfunction "I/O[6]_7") (pintype "bidirectional"))
    )
    (net (code "27") (name "7_SX1") (class "Default")
      (node (ref "R4") (pin "2") (pinfunction "2_2") (pintype "passive"))
      (node (ref "SWB_4") (pin "3") (pinfunction "3_3") (pintype "passive"))
      (node (ref "SWITCH_M4") (pin "2") (pinfunction "2_2") (pintype "passive"))
      (node (ref "SWR_4") (pin "2") (pinfunction "2_2") (pintype "passive"))
      (node (ref "U1") (pin "8") (pinfunction "I/O[7]_8") (pintype "bidirectional"))
    )
    (net (code "28") (name "7_SX2") (class "Default")
      (node (ref "R8") (pin "2") (pinfunction "2_2") (pintype "passive"))
      (node (ref "SWB_8") (pin "3") (pinfunction "3_3") (pintype "passive"))
      (node (ref "SWITCH_M8") (pin "2") (pinfunction "2_2") (pintype "passive"))
      (node (ref "SWR_8") (pin "2") (pinfunction "2_2") (pintype "passive"))
      (node (ref "U2") (pin "8") (pinfunction "I/O[7]_8") (pintype "bidirectional"))
    )
    (net (code "29") (name "7_SX3") (class "Default")
      (node (ref "R29") (pin "1") (pinfunction "1_1") (pintype "passive"))
      (node (ref "SW1") (pin "19") (pinfunction "19_19") (pintype "passive"))
      (node (ref "U4") (pin "8") (pinfunction "I/O[7]_8") (pintype "bidirectional"))
    )
    (net (code "30") (name "8_SX1") (class "Default")
      (node (ref "R1") (pin "2") (pinfunction "2_2") (pintype "passive"))
      (node (ref "SWB_1") (pin "3") (pinfunction "3_3") (pintype "passive"))
      (node (ref "SWITCH_M1") (pin "2") (pinfunction "2_2") (pintype "passive"))
      (node (ref "SWR_1") (pin "2") (pinfunction "2_2") (pintype "passive"))
      (node (ref "U1") (pin "13") (pinfunction "I/O[8]_13") (pintype "bidirectional"))
    )
    (net (code "31") (name "8_SX2") (class "Default")
      (node (ref "R5") (pin "2") (pinfunction "2_2") (pintype "passive"))
      (node (ref "SWB_5") (pin "3") (pinfunction "3_3") (pintype "passive"))
      (node (ref "SWITCH_M5") (pin "2") (pinfunction "2_2") (pintype "passive"))
      (node (ref "SWR_5") (pin "2") (pinfunction "2_2") (pintype "passive"))
      (node (ref "U2") (pin "13") (pinfunction "I/O[8]_13") (pintype "bidirectional"))
    )
    (net (code "32") (name "8_SX3") (class "Default")
      (node (ref "R30") (pin "1") (pinfunction "1_1") (pintype "passive"))
      (node (ref "SW1") (pin "18") (pinfunction "18_18") (pintype "passive"))
      (node (ref "U4") (pin "13") (pinfunction "I/O[8]_13") (pintype "bidirectional"))
    )
    (net (code "33") (name "9_SX1") (class "Default")
      (node (ref "R3") (pin "2") (pinfunction "2_2") (pintype "passive"))
      (node (ref "SWB_3") (pin "3") (pinfunction "3_3") (pintype "passive"))
      (node (ref "SWITCH_M3") (pin "2") (pinfunction "2_2") (pintype "passive"))
      (node (ref "SWR_3") (pin "2") (pinfunction "2_2") (pintype "passive"))
      (node (ref "U1") (pin "14") (pinfunction "I/O[9]_14") (pintype "bidirectional"))
    )
    (net (code "34") (name "9_SX2") (class "Default")
      (node (ref "R7") (pin "2") (pinfunction "2_2") (pintype "passive"))
      (node (ref "SWB_7") (pin "3") (pinfunction "3_3") (pintype "passive"))
      (node (ref "SWITCH_M7") (pin "2") (pinfunction "2_2") (pintype "passive"))
      (node (ref "SWR_7") (pin "2") (pinfunction "2_2") (pintype "passive"))
      (node (ref "U2") (pin "14") (pinfunction "I/O[9]_14") (pintype "bidirectional"))
    )
    (net (code "35") (name "9_SX3") (class "Default")
      (node (ref "R31") (pin "1") (pinfunction "1_1") (pintype "passive"))
      (node (ref "SW1") (pin "17") (pinfunction "17_17") (pintype "passive"))
      (node (ref "U4") (pin "14") (pinfunction "I/O[9]_14") (pintype "bidirectional"))
    )
    (net (code "36") (name "10_SX1") (class "Default")
      (node (ref "M_01") (pin "6") (pinfunction "6_6") (pintype "passive"))
      (node (ref "U1") (pin "15") (pinfunction "I/O[10]_15") (pintype "bidirectional"))
    )
    (net (code "37") (name "10_SX2") (class "Default")
      (node (ref "M_05") (pin "6") (pinfunction "6_6") (pintype "passive"))
      (node (ref "U2") (pin "15") (pinfunction "I/O[10]_15") (pintype "bidirectional"))
    )
    (net (code "38") (name "10_SX3") (class "Default")
      (node (ref "R32") (pin "1") (pinfunction "1_1") (pintype "passive"))
      (node (ref "SW1") (pin "16") (pinfunction "16_16") (pintype "passive"))
      (node (ref "U4") (pin "15") (pinfunction "I/O[10]_15") (pintype "bidirectional"))
    )
    (net (code "39") (name "11_SX1") (class "Default")
      (node (ref "M_01") (pin "5") (pinfunction "5_5") (pintype "passive"))
      (node (ref "U1") (pin "16") (pinfunction "I/O[11]_16") (pintype "bidirectional"))
    )
    (net (code "40") (name "11_SX2") (class "Default")
      (node (ref "M_05") (pin "5") (pinfunction "5_5") (pintype "passive"))
      (node (ref "U2") (pin "16") (pinfunction "I/O[11]_16") (pintype "bidirectional"))
    )
    (net (code "41") (name "11_SX3") (class "Default")
      (node (ref "R33") (pin "1") (pinfunction "1_1") (pintype "passive"))
      (node (ref "SW1") (pin "15") (pinfunction "15_15") (pintype "passive"))
      (node (ref "U4") (pin "16") (pinfunction "I/O[11]_16") (pintype "bidirectional"))
    )
    (net (code "42") (name "12_SX1") (class "Default")
      (node (ref "M_01") (pin "4") (pinfunction "4_4") (pintype "passive"))
      (node (ref "U1") (pin "19") (pinfunction "I/O[12]_19") (pintype "bidirectional"))
    )
    (net (code "43") (name "12_SX2") (class "Default")
      (node (ref "M_05") (pin "4") (pinfunction "4_4") (pintype "passive"))
      (node (ref "U2") (pin "19") (pinfunction "I/O[12]_19") (pintype "bidirectional"))
    )
    (net (code "44") (name "12_SX3") (class "Default")
      (node (ref "R34") (pin "1") (pinfunction "1_1") (pintype "passive"))
      (node (ref "SW1") (pin "14") (pinfunction "14_14") (pintype "passive"))
      (node (ref "U4") (pin "19") (pinfunction "I/O[12]_19") (pintype "bidirectional"))
    )
    (net (code "45") (name "13_SX1") (class "Default")
      (node (ref "M_03") (pin "6") (pinfunction "6_6") (pintype "passive"))
      (node (ref "U1") (pin "20") (pinfunction "I/O[13]_20") (pintype "bidirectional"))
    )
    (net (code "46") (name "13_SX2") (class "Default")
      (node (ref "M_07") (pin "6") (pinfunction "6_6") (pintype "passive"))
      (node (ref "U2") (pin "20") (pinfunction "I/O[13]_20") (pintype "bidirectional"))
    )
    (net (code "47") (name "13_SX3") (class "Default")
      (node (ref "R35") (pin "1") (pinfunction "1_1") (pintype "passive"))
      (node (ref "SW1") (pin "13") (pinfunction "13_13") (pintype "passive"))
      (node (ref "U4") (pin "20") (pinfunction "I/O[13]_20") (pintype "bidirectional"))
    )
    (net (code "48") (name "14_SX1") (class "Default")
      (node (ref "M_03") (pin "5") (pinfunction "5_5") (pintype "passive"))
      (node (ref "U1") (pin "21") (pinfunction "I/O[14]_21") (pintype "bidirectional"))
    )
    (net (code "49") (name "14_SX2") (class "Default")
      (node (ref "M_07") (pin "5") (pinfunction "5_5") (pintype "passive"))
      (node (ref "U2") (pin "21") (pinfunction "I/O[14]_21") (pintype "bidirectional"))
    )
    (net (code "50") (name "14_SX3") (class "Default")
      (node (ref "R36") (pin "1") (pinfunction "1_1") (pintype "passive"))
      (node (ref "SW1") (pin "12") (pinfunction "12_12") (pintype "passive"))
      (node (ref "U4") (pin "21") (pinfunction "I/O[14]_21") (pintype "bidirectional"))
    )
    (net (code "51") (name "15_SX1") (class "Default")
      (node (ref "M_03") (pin "4") (pinfunction "4_4") (pintype "passive"))
      (node (ref "U1") (pin "22") (pinfunction "I/O[15]_22") (pintype "bidirectional"))
    )
    (net (code "52") (name "15_SX2") (class "Default")
      (node (ref "M_07") (pin "4") (pinfunction "4_4") (pintype "passive"))
      (node (ref "U2") (pin "22") (pinfunction "I/O[15]_22") (pintype "bidirectional"))
    )
    (net (code "53") (name "15_SX3") (class "Default")
      (node (ref "R37") (pin "1") (pinfunction "1_1") (pintype "passive"))
      (node (ref "SW1") (pin "11") (pinfunction "11_11") (pintype "passive"))
      (node (ref "U4") (pin "22") (pinfunction "I/O[15]_22") (pintype "bidirectional"))
    )
    (net (code "54") (name "ADDR0_SX1") (class "Default")
      (node (ref "JP8") (pin "1") (pinfunction "1_1") (pintype "passive"))
      (node (ref "U1") (pin "26") (pinfunction "ADDR0_26") (pintype "bidirectional"))
    )
    (net (code "55") (name "ADDR0_SX2") (class "Default")
      (node (ref "JP7") (pin "1") (pinfunction "1_1") (pintype "passive"))
      (node (ref "U2") (pin "26") (pinfunction "ADDR0_26") (pintype "bidirectional"))
    )
    (net (code "56") (name "ADDR0_SX3") (class "Default")
      (node (ref "JP11") (pin "1") (pinfunction "1_1") (pintype "passive"))
      (node (ref "U4") (pin "26") (pinfunction "ADDR0_26") (pintype "bidirectional"))
    )
    (net (code "57") (name "ADDR1_SX1") (class "Default")
      (node (ref "JP9") (pin "1") (pinfunction "1_1") (pintype "passive"))
      (node (ref "U1") (pin "10") (pinfunction "ADDR1_10") (pintype "bidirectional"))
    )
    (net (code "58") (name "ADDR1_SX2") (class "Default")
      (node (ref "JP6") (pin "1") (pinfunction "1_1") (pintype "passive"))
      (node (ref "U2") (pin "10") (pinfunction "ADDR1_10") (pintype "bidirectional"))
    )
    (net (code "59") (name "ADDR1_SX3") (class "Default")
      (node (ref "JP10") (pin "1") (pinfunction "1_1") (pintype "passive"))
      (node (ref "U4") (pin "10") (pinfunction "ADDR1_10") (pintype "bidirectional"))
    )
    (net (code "60") (name "CAN_RX2") (class "Default")
      (node (ref "J1") (pin "4") (pinfunction "4_4") (pintype "passive"))
      (node (ref "JP3") (pin "4") (pinfunction "4_4") (pintype "passive"))
    )
    (net (code "61") (name "CAN_TX2") (class "Default")
      (node (ref "J1") (pin "3") (pinfunction "3_3") (pintype "passive"))
      (node (ref "JP3") (pin "3") (pinfunction "3_3") (pintype "passive"))
    )
    (net (code "62") (name "GND_MCU") (class "Default")
      (node (ref "C1") (pin "2") (pinfunction "2_2") (pintype "passive"))
      (node (ref "C2") (pin "2") (pinfunction "2_2") (pintype "passive"))
      (node (ref "C3") (pin "2") (pinfunction "2_2") (pintype "passive"))
      (node (ref "C4") (pin "2") (pinfunction "2_2") (pintype "passive"))
      (node (ref "C5") (pin "2") (pinfunction "2_2") (pintype "passive"))
      (node (ref "C6") (pin "2") (pinfunction "2_2") (pintype "passive"))
      (node (ref "C7") (pin "2") (pinfunction "2_2") (pintype "passive"))
      (node (ref "C8") (pin "2") (pinfunction "2_2") (pintype "passive"))
      (node (ref "C9") (pin "2") (pinfunction "2_2") (pintype "passive"))
      (node (ref "J1") (pin "11") (pinfunction "11_11") (pintype "passive"))
      (node (ref "J1") (pin "9") (pinfunction "9_9") (pintype "passive"))
      (node (ref "J2") (pin "11") (pinfunction "11_11") (pintype "passive"))
      (node (ref "J2") (pin "9") (pinfunction "9_9") (pintype "passive"))
      (node (ref "JP3") (pin "2") (pinfunction "2_2") (pintype "passive"))
      (node (ref "JP7") (pin "2") (pinfunction "2_2") (pintype "passive"))
      (node (ref "JP9") (pin "2") (pinfunction "2_2") (pintype "passive"))
      (node (ref "M_01") (pin "1") (pinfunction "1_1") (pintype "passive"))
      (node (ref "M_02") (pin "1") (pinfunction "1_1") (pintype "passive"))
      (node (ref "M_03") (pin "1") (pinfunction "1_1") (pintype "passive"))
      (node (ref "M_04") (pin "1") (pinfunction "1_1") (pintype "passive"))
      (node (ref "M_05") (pin "1") (pinfunction "1_1") (pintype "passive"))
      (node (ref "M_06") (pin "1") (pinfunction "1_1") (pintype "passive"))
      (node (ref "M_07") (pin "1") (pinfunction "1_1") (pintype "passive"))
      (node (ref "M_08") (pin "1") (pinfunction "1_1") (pintype "passive"))
      (node (ref "M_09") (pin "1") (pinfunction "1_1") (pintype "passive"))
      (node (ref "POWE_3.3") (pin "2") (pinfunction "C_2") (pintype "passive"))
      (node (ref "R1") (pin "1") (pinfunction "1_1") (pintype "passive"))
      (node (ref "R2") (pin "1") (pinfunction "1_1") (pintype "passive"))
      (node (ref "R22") (pin "1") (pinfunction "1_1") (pintype "passive"))
      (node (ref "R3") (pin "1") (pinfunction "1_1") (pintype "passive"))
      (node (ref "R4") (pin "1") (pinfunction "1_1") (pintype "passive"))
      (node (ref "R5") (pin "1") (pinfunction "1_1") (pintype "passive"))
      (node (ref "R6") (pin "1") (pinfunction "1_1") (pintype "passive"))
      (node (ref "R7") (pin "1") (pinfunction "1_1") (pintype "passive"))
      (node (ref "R8") (pin "1") (pinfunction "1_1") (pintype "passive"))
      (node (ref "STATUS_LED") (pin "2") (pinfunction "C_2") (pintype "passive"))
      (node (ref "SW1") (pin "1") (pinfunction "1_1") (pintype "passive"))
      (node (ref "SW1") (pin "10") (pinfunction "10_10") (pintype "passive"))
      (node (ref "SW1") (pin "2") (pinfunction "2_2") (pintype "passive"))
      (node (ref "SW1") (pin "3") (pinfunction "3_3") (pintype "passive"))
      (node (ref "SW1") (pin "4") (pinfunction "4_4") (pintype "passive"))
      (node (ref "SW1") (pin "5") (pinfunction "5_5") (pintype "passive"))
      (node (ref "SW1") (pin "6") (pinfunction "6_6") (pintype "passive"))
      (node (ref "SW1") (pin "7") (pinfunction "7_7") (pintype "passive"))
      (node (ref "SW1") (pin "8") (pinfunction "8_8") (pintype "passive"))
      (node (ref "SW1") (pin "9") (pinfunction "9_9") (pintype "passive"))
      (node (ref "SWR_1") (pin "1") (pinfunction "1_1") (pintype "passive"))
      (node (ref "SWR_2") (pin "1") (pinfunction "1_1") (pintype "passive"))
      (node (ref "SWR_3") (pin "1") (pinfunction "1_1") (pintype "passive"))
      (node (ref "SWR_4") (pin "1") (pinfunction "1_1") (pintype "passive"))
      (node (ref "SWR_5") (pin "1") (pinfunction "1_1") (pintype "passive"))
      (node (ref "SWR_6") (pin "1") (pinfunction "1_1") (pintype "passive"))
      (node (ref "SWR_7") (pin "1") (pinfunction "1_1") (pintype "passive"))
      (node (ref "SWR_8") (pin "1") (pinfunction "1_1") (pintype "passive"))
      (node (ref "U1") (pin "17") (pinfunction "GND_17") (pintype "bidirectional"))
      (node (ref "U1") (pin "29") (pinfunction "GND_29") (pintype "bidirectional"))
      (node (ref "U1") (pin "3") (pinfunction "GND_3") (pintype "bidirectional"))
      (node (ref "U2") (pin "17") (pinfunction "GND_17") (pintype "bidirectional"))
      (node (ref "U2") (pin "29") (pinfunction "GND_29") (pintype "bidirectional"))
      (node (ref "U2") (pin "3") (pinfunction "GND_3") (pintype "bidirectional"))
      (node (ref "U4") (pin "17") (pinfunction "GND_17") (pintype "bidirectional"))
      (node (ref "U4") (pin "29") (pinfunction "GND_29") (pintype "bidirectional"))
      (node (ref "U4") (pin "3") (pinfunction "GND_3") (pintype "bidirectional"))
    )
    (net (code "63") (name "INT_01") (class "Default")
      (node (ref "J1") (pin "6") (pinfunction "6_6") (pintype "passive"))
      (node (ref "JP2") (pin "1") (pinfunction "1_1") (pintype "passive"))
      (node (ref "M_09") (pin "5") (pinfunction "5_5") (pintype "passive"))
      (node (ref "R12") (pin "1") (pinfunction "1_1") (pintype "passive"))
      (node (ref "U1") (pin "9") (pinfunction "~{INT}_9") (pintype "bidirectional"))
    )
    (net (code "64") (name "INT_02") (class "Default")
      (node (ref "J1") (pin "5") (pinfunction "5_5") (pintype "passive"))
      (node (ref "JP2") (pin "2") (pinfunction "2_2") (pintype "passive"))
      (node (ref "M_09") (pin "6") (pinfunction "6_6") (pintype "passive"))
      (node (ref "R19") (pin "1") (pinfunction "1_1") (pintype "passive"))
      (node (ref "U2") (pin "9") (pinfunction "~{INT}_9") (pintype "bidirectional"))
    )
    (net (code "65") (name "NEOPIXEL_01") (class "Default")
      (node (ref "J2") (pin "2") (pinfunction "2_2") (pintype "passive"))
      (node (ref "M_01") (pin "3") (pinfunction "3_3") (pintype "passive"))
    )
    (net (code "66") (name "NEOPIXEL_02") (class "Default")
      (node (ref "J2") (pin "1") (pinfunction "1_1") (pintype "passive"))
      (node (ref "M_02") (pin "3") (pinfunction "3_3") (pintype "passive"))
    )
    (net (code "67") (name "NEOPIXEL_03") (class "Default")
      (node (ref "J2") (pin "4") (pinfunction "4_4") (pintype "passive"))
      (node (ref "M_03") (pin "3") (pinfunction "3_3") (pintype "passive"))
    )
    (net (code "68") (name "NEOPIXEL_04") (class "Default")
      (node (ref "J2") (pin "3") (pinfunction "3_3") (pintype "passive"))
      (node (ref "M_04") (pin "3") (pinfunction "3_3") (pintype "passive"))
    )
    (net (code "69") (name "NEOPIXEL_05") (class "Default")
      (node (ref "J2") (pin "6") (pinfunction "6_6") (pintype "passive"))
      (node (ref "M_05") (pin "3") (pinfunction "3_3") (pintype "passive"))
    )
    (net (code "70") (name "NEOPIXEL_06") (class "Default")
      (node (ref "J2") (pin "5") (pinfunction "5_5") (pintype "passive"))
      (node (ref "M_06") (pin "3") (pinfunction "3_3") (pintype "passive"))
    )
    (net (code "71") (name "NEOPIXEL_07") (class "Default")
      (node (ref "J2") (pin "8") (pinfunction "8_8") (pintype "passive"))
      (node (ref "M_07") (pin "3") (pinfunction "3_3") (pintype "passive"))
    )
    (net (code "72") (name "NEOPIXEL_08") (class "Default")
      (node (ref "J2") (pin "7") (pinfunction "7_7") (pintype "passive"))
      (node (ref "M_08") (pin "3") (pinfunction "3_3") (pintype "passive"))
    )
    (net (code "73") (name "Net-(JP6-Pad2)") (class "Default")
      (node (ref "JP6") (pin "2") (pinfunction "2_2") (pintype "passive"))
      (node (ref "R21") (pin "1") (pinfunction "1_1") (pintype "passive"))
    )
    (net (code "74") (name "Net-(JP8-Pad2)") (class "Default")
      (node (ref "JP8") (pin "2") (pinfunction "2_2") (pintype "passive"))
      (node (ref "R13") (pin "1") (pinfunction "1_1") (pintype "passive"))
    )
    (net (code "75") (name "Net-(JP10-Pad2)") (class "Default")
      (node (ref "JP10") (pin "2") (pinfunction "2_2") (pintype "passive"))
      (node (ref "R25") (pin "1") (pinfunction "1_1") (pintype "passive"))
    )
    (net (code "76") (name "Net-(JP11-Pad2)") (class "Default")
      (node (ref "JP11") (pin "2") (pinfunction "2_2") (pintype "passive"))
      (node (ref "R26") (pin "1") (pinfunction "1_1") (pintype "passive"))
    )
    (net (code "77") (name "Net-(POWE_3.3-A)") (class "Default")
      (node (ref "POWE_3.3") (pin "1") (pinfunction "A_1") (pintype "passive"))
      (node (ref "R27") (pin "1") (pinfunction "1_1") (pintype "passive"))
    )
    (net (code "78") (name "Net-(STATUS_LED-A)") (class "Default")
      (node (ref "R28") (pin "1") (pinfunction "1_1") (pintype "passive"))
      (node (ref "STATUS_LED") (pin "1") (pinfunction "A_1") (pintype "passive"))
    )
    (net (code "79") (name "OSCIO_SX1") (class "Default")
      (node (ref "U1") (pin "11") (pinfunction "OSCIO_11") (pintype "bidirectional"))
    )
    (net (code "80") (name "OSCIO_SX2") (class "Default")
      (node (ref "U2") (pin "11") (pinfunction "OSCIO_11") (pintype "bidirectional"))
    )
    (net (code "81") (name "OSCIO_SX3") (class "Default")
      (node (ref "U4") (pin "11") (pinfunction "OSCIO_11") (pintype "bidirectional"))
    )
    (net (code "82") (name "RESET") (class "Default")
      (node (ref "J1") (pin "8") (pinfunction "8_8") (pintype "passive"))
      (node (ref "JP1") (pin "2") (pinfunction "2_2") (pintype "passive"))
      (node (ref "JP1") (pin "3") (pinfunction "3_3") (pintype "passive"))
      (node (ref "R22") (pin "2") (pinfunction "2_2") (pintype "passive"))
      (node (ref "S2") (pin "3") (pinfunction "3_3") (pintype "passive"))
      (node (ref "S2") (pin "4") (pinfunction "4_4") (pintype "passive"))
    )
    (net (code "83") (name "SCL_00") (class "Default")
      (node (ref "J1") (pin "2") (pinfunction "2_2") (pintype "passive"))
      (node (ref "M_09") (pin "4") (pinfunction "4_4") (pintype "passive"))
      (node (ref "R11") (pin "1") (pinfunction "1_1") (pintype "passive"))
      (node (ref "R18") (pin "1") (pinfunction "1_1") (pintype "passive"))
      (node (ref "R23") (pin "1") (pinfunction "1_1") (pintype "passive"))
      (node (ref "U1") (pin "25") (pinfunction "SCL_25") (pintype "bidirectional"))
      (node (ref "U2") (pin "25") (pinfunction "SCL_25") (pintype "bidirectional"))
      (node (ref "U4") (pin "25") (pinfunction "SCL_25") (pintype "bidirectional"))
    )
    (net (code "84") (name "SDA_00") (class "Default")
      (node (ref "J1") (pin "1") (pinfunction "1_1") (pintype "passive"))
      (node (ref "M_09") (pin "3") (pinfunction "3_3") (pintype "passive"))
      (node (ref "R10") (pin "1") (pinfunction "1_1") (pintype "passive"))
      (node (ref "R17") (pin "1") (pinfunction "1_1") (pintype "passive"))
      (node (ref "R20") (pin "1") (pinfunction "1_1") (pintype "passive"))
      (node (ref "U1") (pin "24") (pinfunction "SDA_24") (pintype "bidirectional"))
      (node (ref "U2") (pin "24") (pinfunction "SDA_24") (pintype "bidirectional"))
      (node (ref "U4") (pin "24") (pinfunction "SDA_24") (pintype "bidirectional"))
    )
    (net (code "85") (name "VCC_5V") (class "Default")
      (node (ref "JP3") (pin "1") (pinfunction "1_1") (pintype "passive"))
      (node (ref "M_01") (pin "2") (pinfunction "2_2") (pintype "passive"))
      (node (ref "M_02") (pin "2") (pinfunction "2_2") (pintype "passive"))
      (node (ref "M_03") (pin "2") (pinfunction "2_2") (pintype "passive"))
      (node (ref "M_04") (pin "2") (pinfunction "2_2") (pintype "passive"))
      (node (ref "M_05") (pin "2") (pinfunction "2_2") (pintype "passive"))
      (node (ref "M_06") (pin "2") (pinfunction "2_2") (pintype "passive"))
      (node (ref "M_07") (pin "2") (pinfunction "2_2") (pintype "passive"))
      (node (ref "M_08") (pin "2") (pinfunction "2_2") (pintype "passive"))
      (node (ref "S1") (pin "4") (pinfunction "4_4") (pintype "passive"))
      (node (ref "S1") (pin "8") (pinfunction "8_8") (pintype "passive"))
    )
    (net (code "86") (name "VCC_5V_IN") (class "Default")
      (node (ref "J1") (pin "12") (pinfunction "12_12") (pintype "passive"))
      (node (ref "J2") (pin "12") (pinfunction "12_12") (pintype "passive"))
      (node (ref "S1") (pin "3") (pinfunction "3_3") (pintype "passive"))
      (node (ref "S1") (pin "7") (pinfunction "7_7") (pintype "passive"))
    )
    (net (code "87") (name "unconnected-(S1-Pad1)") (class "Default")
      (node (ref "S1") (pin "1") (pinfunction "1_1") (pintype "passive"))
    )
    (net (code "88") (name "unconnected-(S1-Pad2)") (class "Default")
      (node (ref "S1") (pin "2") (pinfunction "2_2") (pintype "passive"))
    )
    (net (code "89") (name "unconnected-(S1-Pad5)") (class "Default")
      (node (ref "S1") (pin "5") (pinfunction "5_5") (pintype "passive"))
    )
    (net (code "90") (name "unconnected-(S1-Pad6)") (class "Default")
      (node (ref "S1") (pin "6") (pinfunction "6_6") (pintype "passive"))
    )
    (net (code "91") (name "unconnected-(SWB_1-Pad2)") (class "Default")
      (node (ref "SWB_1") (pin "2") (pinfunction "2_2") (pintype "passive"))
    )
    (net (code "92") (name "unconnected-(SWB_1-Pad4)") (class "Default")
      (node (ref "SWB_1") (pin "4") (pinfunction "4_4") (pintype "passive"))
    )
    (net (code "93") (name "unconnected-(SWB_2-Pad2)") (class "Default")
      (node (ref "SWB_2") (pin "2") (pinfunction "2_2") (pintype "passive"))
    )
    (net (code "94") (name "unconnected-(SWB_2-Pad4)") (class "Default")
      (node (ref "SWB_2") (pin "4") (pinfunction "4_4") (pintype "passive"))
    )
    (net (code "95") (name "unconnected-(SWB_3-Pad2)") (class "Default")
      (node (ref "SWB_3") (pin "2") (pinfunction "2_2") (pintype "passive"))
    )
    (net (code "96") (name "unconnected-(SWB_3-Pad4)") (class "Default")
      (node (ref "SWB_3") (pin "4") (pinfunction "4_4") (pintype "passive"))
    )
    (net (code "97") (name "unconnected-(SWB_4-Pad2)") (class "Default")
      (node (ref "SWB_4") (pin "2") (pinfunction "2_2") (pintype "passive"))
    )
    (net (code "98") (name "unconnected-(SWB_4-Pad4)") (class "Default")
      (node (ref "SWB_4") (pin "4") (pinfunction "4_4") (pintype "passive"))
    )
    (net (code "99") (name "unconnected-(SWB_5-Pad2)") (class "Default")
      (node (ref "SWB_5") (pin "2") (pinfunction "2_2") (pintype "passive"))
    )
    (net (code "100") (name "unconnected-(SWB_5-Pad4)") (class "Default")
      (node (ref "SWB_5") (pin "4") (pinfunction "4_4") (pintype "passive"))
    )
    (net (code "101") (name "unconnected-(SWB_6-Pad2)") (class "Default")
      (node (ref "SWB_6") (pin "2") (pinfunction "2_2") (pintype "passive"))
    )
    (net (code "102") (name "unconnected-(SWB_6-Pad4)") (class "Default")
      (node (ref "SWB_6") (pin "4") (pinfunction "4_4") (pintype "passive"))
    )
    (net (code "103") (name "unconnected-(SWB_7-Pad2)") (class "Default")
      (node (ref "SWB_7") (pin "2") (pinfunction "2_2") (pintype "passive"))
    )
    (net (code "104") (name "unconnected-(SWB_7-Pad4)") (class "Default")
      (node (ref "SWB_7") (pin "4") (pinfunction "4_4") (pintype "passive"))
    )
    (net (code "105") (name "unconnected-(SWB_8-Pad2)") (class "Default")
      (node (ref "SWB_8") (pin "2") (pinfunction "2_2") (pintype "passive"))
    )
    (net (code "106") (name "unconnected-(SWB_8-Pad4)") (class "Default")
      (node (ref "SWB_8") (pin "4") (pinfunction "4_4") (pintype "passive"))
    )
  )
)
